# XibecaModuleBottom.net
KiCad netlist of a schematic drawn in EAGLE
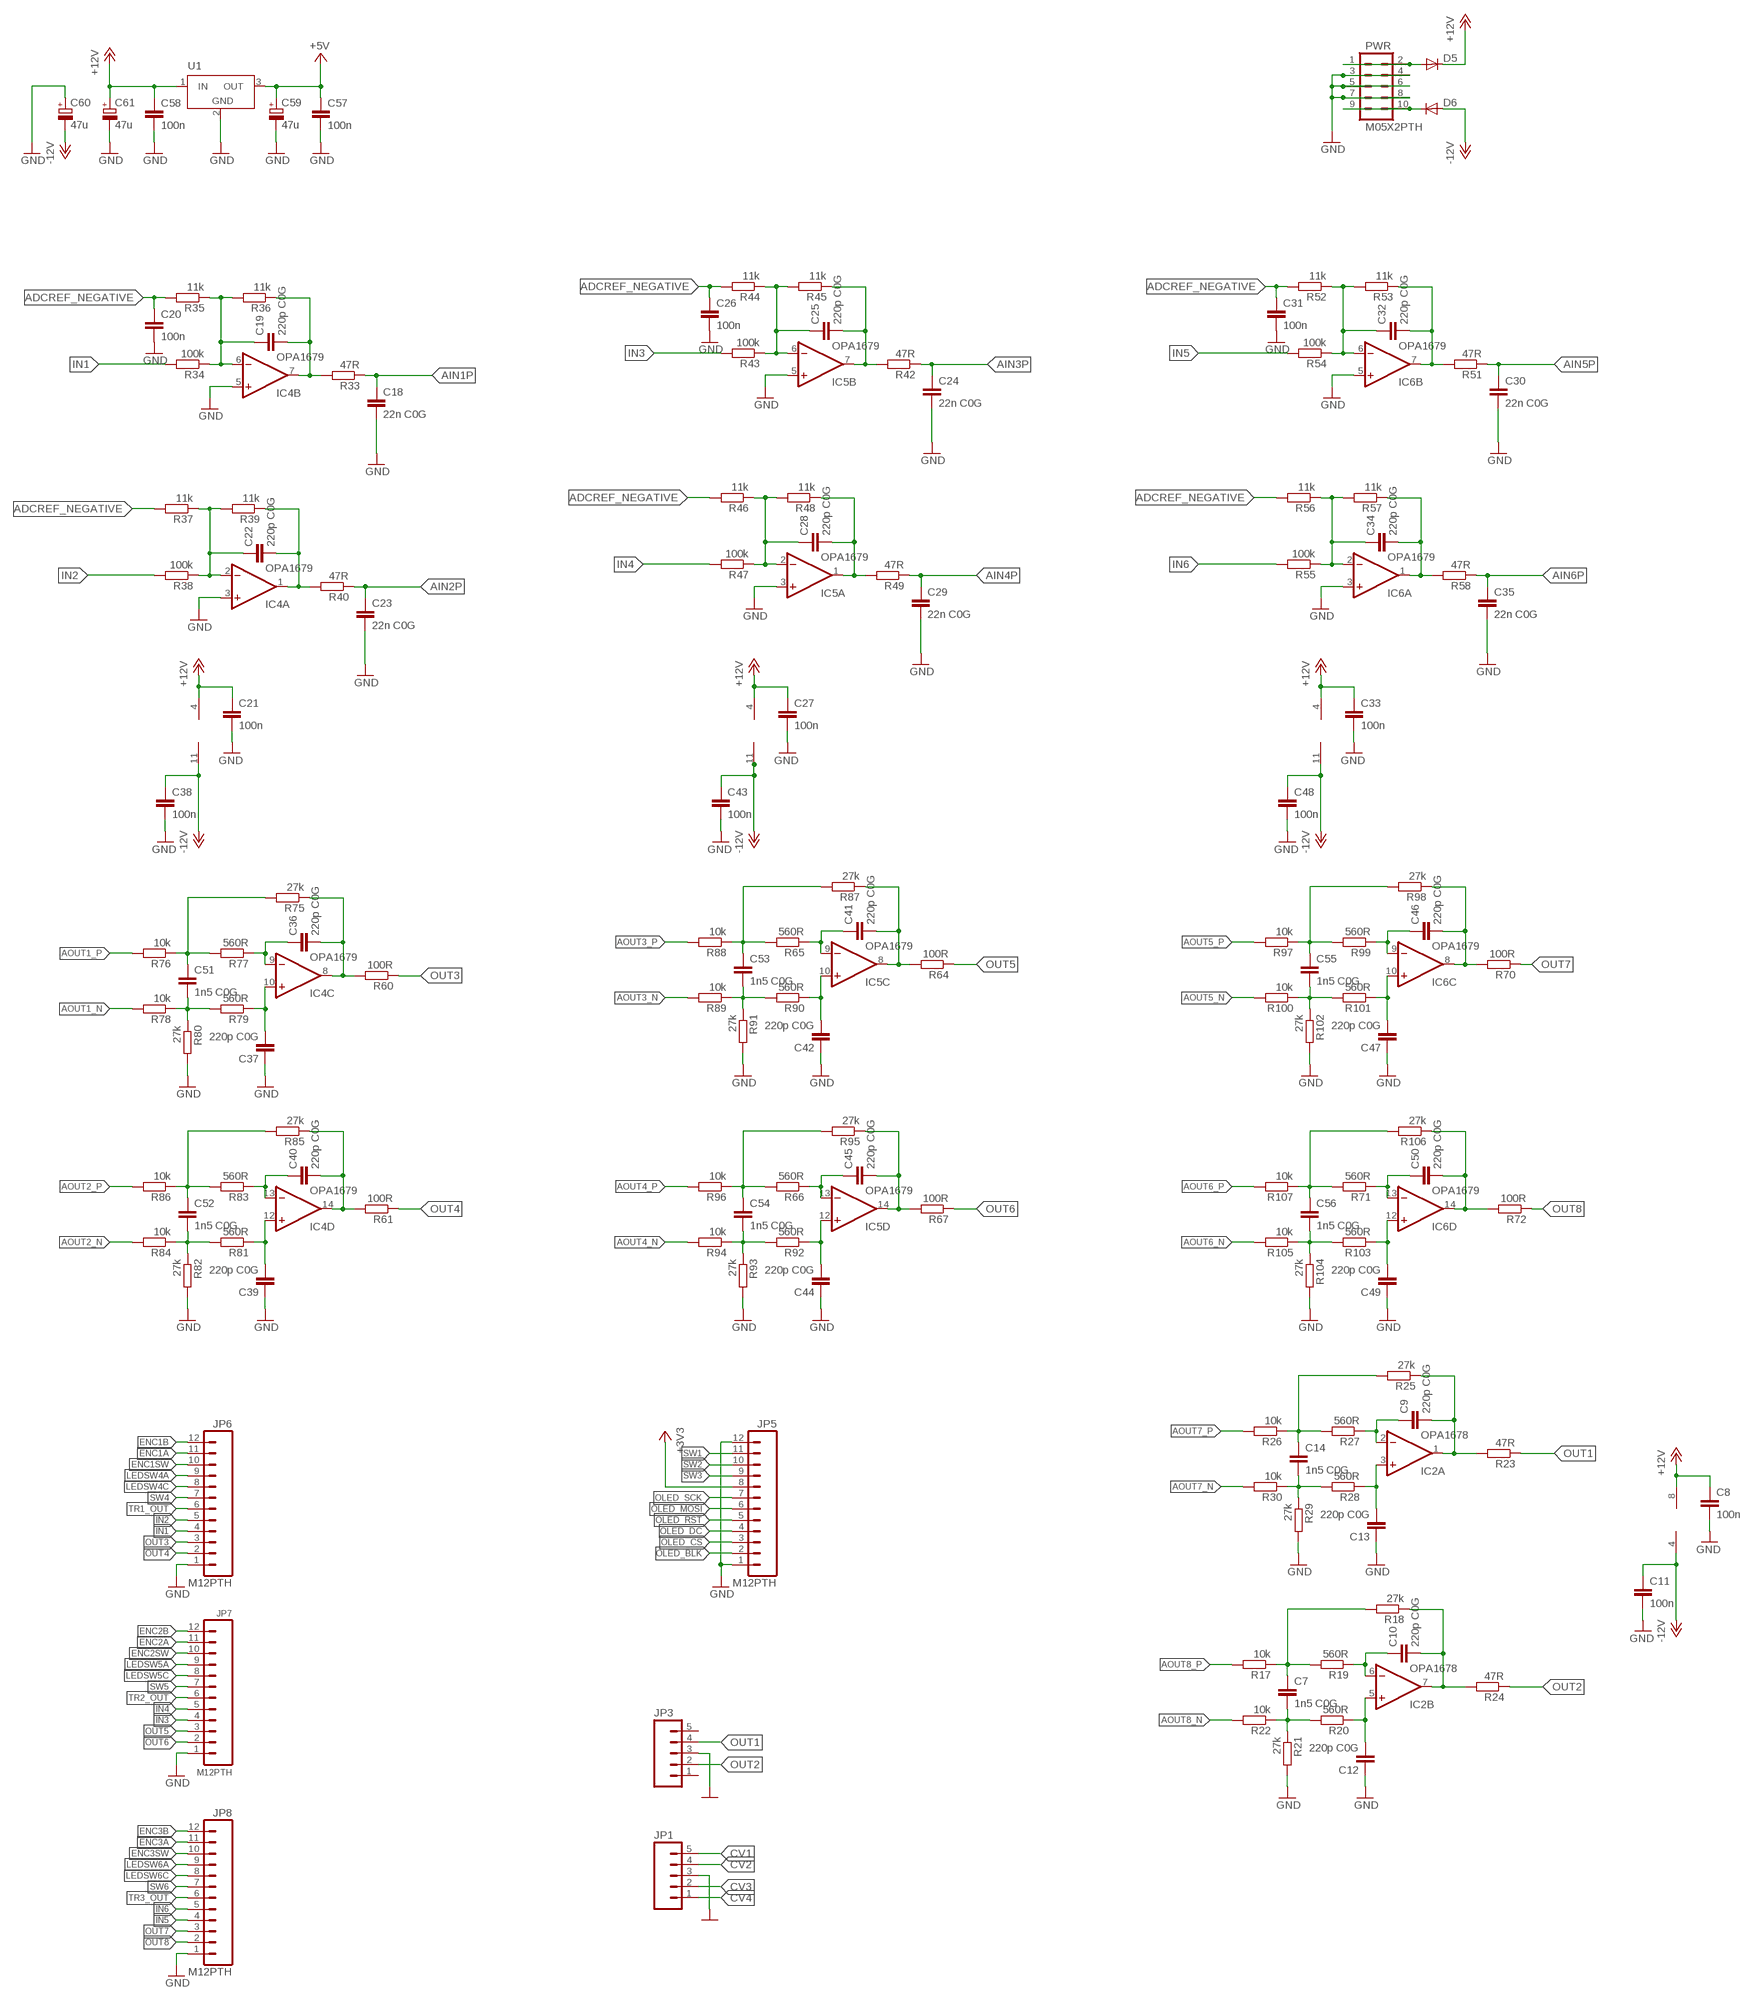
[diagram p0: schematic, sheet 1, part 1 of 2]
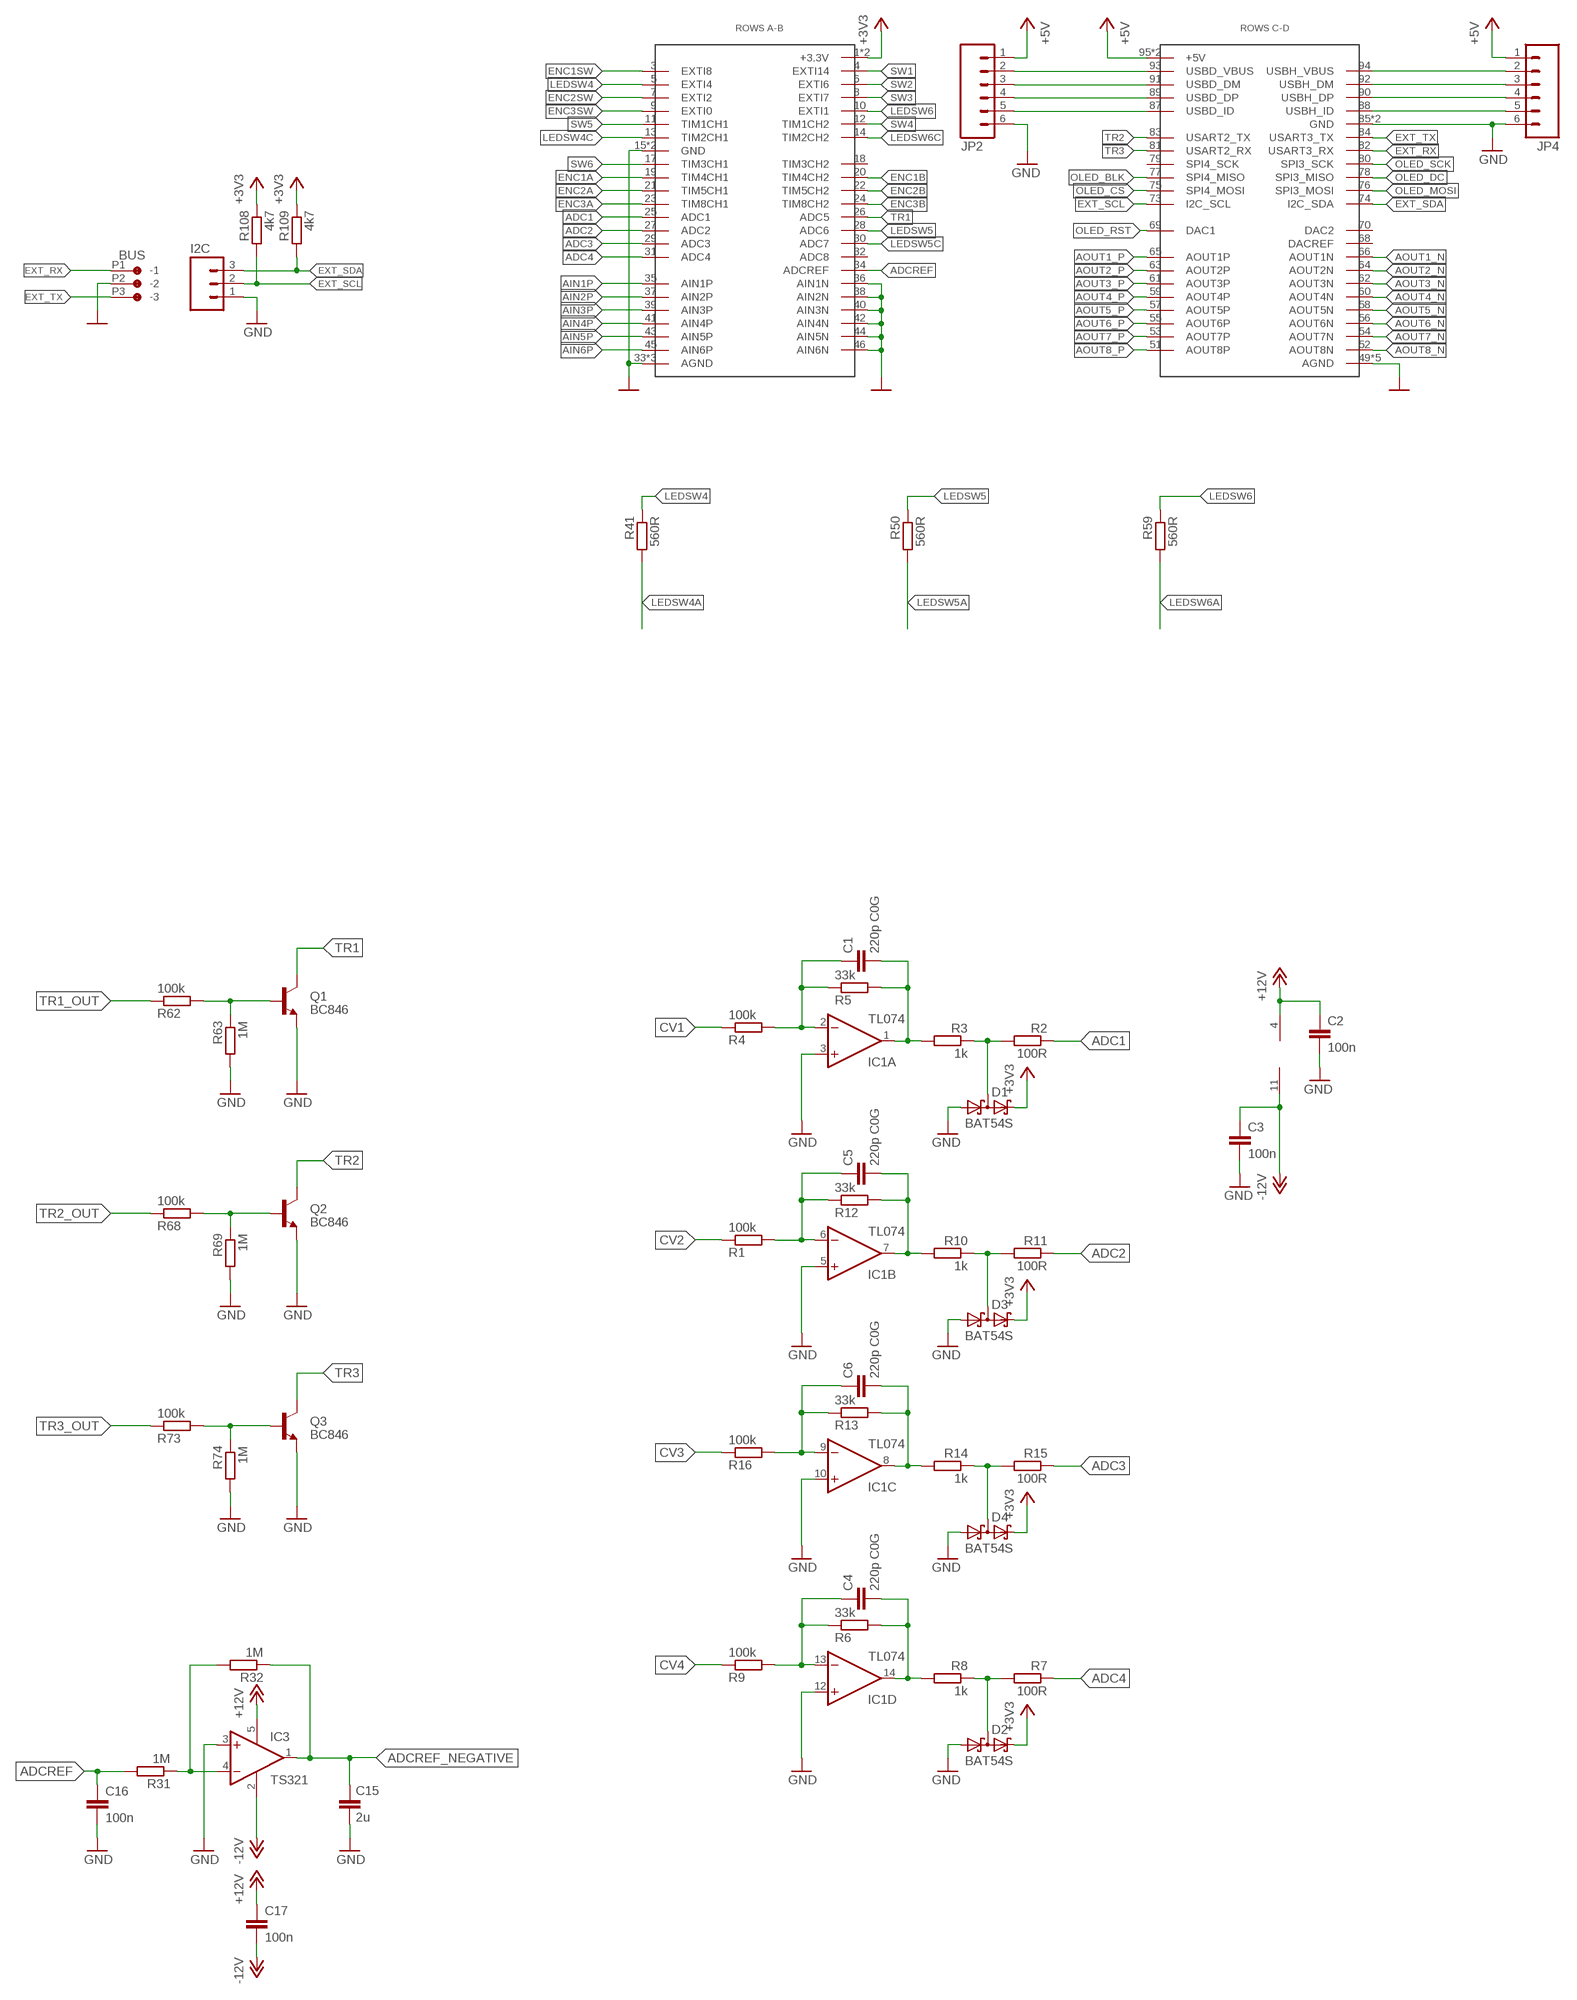
[diagram p1: schematic, sheet 1, part 2 of 2]

(export (version "E")
  (design (tool "Eeschema 10.0.6"))
  (components
    (comp (ref "BUS")
      (value "CON-JST_PH_3W")
      (footprint "eagle-import:CON-JST_PH_3W")
      (libsource (lib "eagle-import") (part "CON-JST_PH_3W"))
    )
    (comp (ref "C1")
      (value "220p C0G")
      (footprint "eagle-import:C0603")
      (libsource (lib "eagle-import") (part "Rebel_15457297_C-EUC0603"))
    )
    (comp (ref "C2")
      (value "100n")
      (footprint "eagle-import:C0603")
      (libsource (lib "eagle-import") (part "Rebel_15457297_C-EUC0603"))
    )
    (comp (ref "C3")
      (value "100n")
      (footprint "eagle-import:C0603")
      (libsource (lib "eagle-import") (part "Rebel_15457297_C-EUC0603"))
    )
    (comp (ref "C4")
      (value "220p C0G")
      (footprint "eagle-import:C0603")
      (libsource (lib "eagle-import") (part "Rebel_15457297_C-EUC0603"))
    )
    (comp (ref "C5")
      (value "220p C0G")
      (footprint "eagle-import:C0603")
      (libsource (lib "eagle-import") (part "Rebel_15457297_C-EUC0603"))
    )
    (comp (ref "C6")
      (value "220p C0G")
      (footprint "eagle-import:C0603")
      (libsource (lib "eagle-import") (part "Rebel_15457297_C-EUC0603"))
    )
    (comp (ref "C7")
      (value "1n5 C0G")
      (footprint "eagle-import:C0603")
      (libsource (lib "eagle-import") (part "Rebel_15457297_C-EUC0603"))
    )
    (comp (ref "C8")
      (value "100n")
      (footprint "eagle-import:C0603")
      (libsource (lib "eagle-import") (part "Rebel_15457297_C-EUC0603"))
    )
    (comp (ref "C9")
      (value "220p C0G")
      (footprint "eagle-import:C0603")
      (libsource (lib "eagle-import") (part "Rebel_15457297_C-EUC0603"))
    )
    (comp (ref "C10")
      (value "220p C0G")
      (footprint "eagle-import:C0603")
      (libsource (lib "eagle-import") (part "Rebel_15457297_C-EUC0603"))
    )
    (comp (ref "C11")
      (value "100n")
      (footprint "eagle-import:C0603")
      (libsource (lib "eagle-import") (part "Rebel_15457297_C-EUC0603"))
    )
    (comp (ref "C12")
      (value "220p C0G")
      (footprint "eagle-import:C0603")
      (libsource (lib "eagle-import") (part "Rebel_15457297_C-EUC0603"))
    )
    (comp (ref "C13")
      (value "220p C0G")
      (footprint "eagle-import:C0603")
      (libsource (lib "eagle-import") (part "Rebel_15457297_C-EUC0603"))
    )
    (comp (ref "C14")
      (value "1n5 C0G")
      (footprint "eagle-import:C0603")
      (libsource (lib "eagle-import") (part "Rebel_15457297_C-EUC0603"))
    )
    (comp (ref "C15")
      (value "2u")
      (footprint "eagle-import:C0603")
      (libsource (lib "eagle-import") (part "C-EUC0603"))
    )
    (comp (ref "C16")
      (value "100n")
      (footprint "eagle-import:C0603")
      (libsource (lib "eagle-import") (part "Rebel_15457297_C-EUC0603"))
    )
    (comp (ref "C17")
      (value "100n")
      (footprint "eagle-import:C0603")
      (libsource (lib "eagle-import") (part "Rebel_15457297_C-EUC0603"))
    )
    (comp (ref "C18")
      (value "22n C0G")
      (footprint "eagle-import:C0603")
      (libsource (lib "eagle-import") (part "Rebel_15457297_C-EUC0603"))
    )
    (comp (ref "C19")
      (value "220p C0G")
      (footprint "eagle-import:C0603")
      (libsource (lib "eagle-import") (part "Rebel_15457297_C-EUC0603"))
    )
    (comp (ref "C20")
      (value "100n")
      (footprint "eagle-import:C0603")
      (libsource (lib "eagle-import") (part "Rebel_15457297_C-EUC0603"))
    )
    (comp (ref "C21")
      (value "100n")
      (footprint "eagle-import:C0603")
      (libsource (lib "eagle-import") (part "C-EUC0603"))
    )
    (comp (ref "C22")
      (value "220p C0G")
      (footprint "eagle-import:C0603")
      (libsource (lib "eagle-import") (part "Rebel_15457297_C-EUC0603"))
    )
    (comp (ref "C23")
      (value "22n C0G")
      (footprint "eagle-import:C0603")
      (libsource (lib "eagle-import") (part "Rebel_15457297_C-EUC0603"))
    )
    (comp (ref "C24")
      (value "22n C0G")
      (footprint "eagle-import:C0603")
      (libsource (lib "eagle-import") (part "Rebel_15457297_C-EUC0603"))
    )
    (comp (ref "C25")
      (value "220p C0G")
      (footprint "eagle-import:C0603")
      (libsource (lib "eagle-import") (part "Rebel_15457297_C-EUC0603"))
    )
    (comp (ref "C26")
      (value "100n")
      (footprint "eagle-import:C0603")
      (libsource (lib "eagle-import") (part "Rebel_15457297_C-EUC0603"))
    )
    (comp (ref "C27")
      (value "100n")
      (footprint "eagle-import:C0603")
      (libsource (lib "eagle-import") (part "Rebel_15457297_C-EUC0603"))
    )
    (comp (ref "C28")
      (value "220p C0G")
      (footprint "eagle-import:C0603")
      (libsource (lib "eagle-import") (part "Rebel_15457297_C-EUC0603"))
    )
    (comp (ref "C29")
      (value "22n C0G")
      (footprint "eagle-import:C0603")
      (libsource (lib "eagle-import") (part "Rebel_15457297_C-EUC0603"))
    )
    (comp (ref "C30")
      (value "22n C0G")
      (footprint "eagle-import:C0603")
      (libsource (lib "eagle-import") (part "Rebel_15457297_C-EUC0603"))
    )
    (comp (ref "C31")
      (value "100n")
      (footprint "eagle-import:C0603")
      (libsource (lib "eagle-import") (part "Rebel_15457297_C-EUC0603"))
    )
    (comp (ref "C32")
      (value "220p C0G")
      (footprint "eagle-import:C0603")
      (libsource (lib "eagle-import") (part "Rebel_15457297_C-EUC0603"))
    )
    (comp (ref "C33")
      (value "100n")
      (footprint "eagle-import:C0603")
      (libsource (lib "eagle-import") (part "C-EUC0603"))
    )
    (comp (ref "C34")
      (value "220p C0G")
      (footprint "eagle-import:C0603")
      (libsource (lib "eagle-import") (part "Rebel_15457297_C-EUC0603"))
    )
    (comp (ref "C35")
      (value "22n C0G")
      (footprint "eagle-import:C0603")
      (libsource (lib "eagle-import") (part "Rebel_15457297_C-EUC0603"))
    )
    (comp (ref "C36")
      (value "220p C0G")
      (footprint "eagle-import:C0603")
      (libsource (lib "eagle-import") (part "Rebel_15457297_C-EUC0603"))
    )
    (comp (ref "C37")
      (value "220p C0G")
      (footprint "eagle-import:C0603")
      (libsource (lib "eagle-import") (part "Rebel_15457297_C-EUC0603"))
    )
    (comp (ref "C38")
      (value "100n")
      (footprint "eagle-import:C0603")
      (libsource (lib "eagle-import") (part "C-EUC0603"))
    )
    (comp (ref "C39")
      (value "220p C0G")
      (footprint "eagle-import:C0603")
      (libsource (lib "eagle-import") (part "Rebel_15457297_C-EUC0603"))
    )
    (comp (ref "C40")
      (value "220p C0G")
      (footprint "eagle-import:C0603")
      (libsource (lib "eagle-import") (part "Rebel_15457297_C-EUC0603"))
    )
    (comp (ref "C41")
      (value "220p C0G")
      (footprint "eagle-import:C0603")
      (libsource (lib "eagle-import") (part "Rebel_15457297_C-EUC0603"))
    )
    (comp (ref "C42")
      (value "220p C0G")
      (footprint "eagle-import:C0603")
      (libsource (lib "eagle-import") (part "Rebel_15457297_C-EUC0603"))
    )
    (comp (ref "C43")
      (value "100n")
      (footprint "eagle-import:C0603")
      (libsource (lib "eagle-import") (part "Rebel_15457297_C-EUC0603"))
    )
    (comp (ref "C44")
      (value "220p C0G")
      (footprint "eagle-import:C0603")
      (libsource (lib "eagle-import") (part "Rebel_15457297_C-EUC0603"))
    )
    (comp (ref "C45")
      (value "220p C0G")
      (footprint "eagle-import:C0603")
      (libsource (lib "eagle-import") (part "Rebel_15457297_C-EUC0603"))
    )
    (comp (ref "C46")
      (value "220p C0G")
      (footprint "eagle-import:C0603")
      (libsource (lib "eagle-import") (part "Rebel_15457297_C-EUC0603"))
    )
    (comp (ref "C47")
      (value "220p C0G")
      (footprint "eagle-import:C0603")
      (libsource (lib "eagle-import") (part "Rebel_15457297_C-EUC0603"))
    )
    (comp (ref "C48")
      (value "100n")
      (footprint "eagle-import:C0603")
      (libsource (lib "eagle-import") (part "C-EUC0603"))
    )
    (comp (ref "C49")
      (value "220p C0G")
      (footprint "eagle-import:C0603")
      (libsource (lib "eagle-import") (part "Rebel_15457297_C-EUC0603"))
    )
    (comp (ref "C50")
      (value "220p C0G")
      (footprint "eagle-import:C0603")
      (libsource (lib "eagle-import") (part "Rebel_15457297_C-EUC0603"))
    )
    (comp (ref "C51")
      (value "1n5 C0G")
      (footprint "eagle-import:C0603")
      (libsource (lib "eagle-import") (part "Rebel_15457297_C-EUC0603"))
    )
    (comp (ref "C52")
      (value "1n5 C0G")
      (footprint "eagle-import:C0603")
      (libsource (lib "eagle-import") (part "Rebel_15457297_C-EUC0603"))
    )
    (comp (ref "C53")
      (value "1n5 C0G")
      (footprint "eagle-import:C0603")
      (libsource (lib "eagle-import") (part "Rebel_15457297_C-EUC0603"))
    )
    (comp (ref "C54")
      (value "1n5 C0G")
      (footprint "eagle-import:C0603")
      (libsource (lib "eagle-import") (part "Rebel_15457297_C-EUC0603"))
    )
    (comp (ref "C55")
      (value "1n5 C0G")
      (footprint "eagle-import:C0603")
      (libsource (lib "eagle-import") (part "Rebel_15457297_C-EUC0603"))
    )
    (comp (ref "C56")
      (value "1n5 C0G")
      (footprint "eagle-import:C0603")
      (libsource (lib "eagle-import") (part "Rebel_15457297_C-EUC0603"))
    )
    (comp (ref "C57")
      (value "100n")
      (footprint "eagle-import:C0603")
      (libsource (lib "eagle-import") (part "Rebel_15457297_C-EUC0603"))
    )
    (comp (ref "C58")
      (value "100n")
      (footprint "eagle-import:C0603")
      (libsource (lib "eagle-import") (part "Rebel_15457297_C-EUC0603"))
    )
    (comp (ref "C59")
      (value "47u")
      (footprint "eagle-import:E5-8,5")
      (libsource (lib "eagle-import") (part "CPOL-EUE5-8.5"))
    )
    (comp (ref "C60")
      (value "47u")
      (footprint "eagle-import:E5-8,5")
      (libsource (lib "eagle-import") (part "CPOL-EUE5-8.5"))
    )
    (comp (ref "C61")
      (value "47u")
      (footprint "eagle-import:E5-8,5")
      (libsource (lib "eagle-import") (part "CPOL-EUE5-8.5"))
    )
    (comp (ref "D1")
      (value "BAT54S")
      (footprint "eagle-import:SOT23")
      (libsource (lib "eagle-import") (part "BAT54S"))
    )
    (comp (ref "D2")
      (value "BAT54S")
      (footprint "eagle-import:SOT23")
      (libsource (lib "eagle-import") (part "BAT54S"))
    )
    (comp (ref "D3")
      (value "BAT54S")
      (footprint "eagle-import:SOT23")
      (libsource (lib "eagle-import") (part "BAT54S"))
    )
    (comp (ref "D4")
      (value "BAT54S")
      (footprint "eagle-import:SOT23")
      (libsource (lib "eagle-import") (part "BAT54S"))
    )
    (comp (ref "D5")
      (value "DIODE1N4001")
      (footprint "eagle-import:DIODE-1N4001")
      (libsource (lib "eagle-import") (part "DIODE1N4001"))
    )
    (comp (ref "D6")
      (value "DIODE1N4001")
      (footprint "eagle-import:DIODE-1N4001")
      (libsource (lib "eagle-import") (part "DIODE1N4001"))
    )
    (comp (ref "I2C")
      (value "M03PTH")
      (footprint "eagle-import:1X03")
      (libsource (lib "eagle-import") (part "M03PTH"))
    )
    (comp (ref "IC1")
      (value "TL074")
      (footprint "eagle-import:SO14")
      (libsource (lib "eagle-import") (part "QUAD_OPAMPD"))
    )
    (comp (ref "IC2")
      (value "OPA1678")
      (footprint "eagle-import:SO08")
      (libsource (lib "eagle-import") (part "TL072D"))
    )
    (comp (ref "IC3")
      (value "TS321")
      (footprint "eagle-import:SOT23-5")
      (libsource (lib "eagle-import") (part "OPA725DBV"))
    )
    (comp (ref "IC4")
      (value "OPA1679")
      (footprint "eagle-import:SO14")
      (libsource (lib "eagle-import") (part "TL074D"))
    )
    (comp (ref "IC5")
      (value "OPA1679")
      (footprint "eagle-import:SO14")
      (libsource (lib "eagle-import") (part "TL074D"))
    )
    (comp (ref "IC6")
      (value "OPA1679")
      (footprint "eagle-import:SO14")
      (libsource (lib "eagle-import") (part "TL074D"))
    )
    (comp (ref "JP1")
      (value "M05PTH")
      (footprint "eagle-import:1X05")
      (libsource (lib "eagle-import") (part "M05PTH"))
    )
    (comp (ref "JP2")
      (value "M06SIP")
      (footprint "eagle-import:1X06")
      (libsource (lib "eagle-import") (part "M06SIP"))
    )
    (comp (ref "JP3")
      (value "M05PTH")
      (footprint "eagle-import:1X05")
      (libsource (lib "eagle-import") (part "M05PTH"))
    )
    (comp (ref "JP4")
      (value "M06SIP")
      (footprint "eagle-import:1X06")
      (libsource (lib "eagle-import") (part "M06SIP"))
    )
    (comp (ref "JP5")
      (value "M12PTH")
      (footprint "eagle-import:1X12")
      (libsource (lib "eagle-import") (part "M12PTH"))
    )
    (comp (ref "JP6")
      (value "M12PTH")
      (footprint "eagle-import:1X12")
      (libsource (lib "eagle-import") (part "M12PTH"))
    )
    (comp (ref "JP7")
      (value "M12PTH")
      (footprint "eagle-import:1X12")
      (libsource (lib "eagle-import") (part "M12PTH"))
    )
    (comp (ref "JP8")
      (value "M12PTH")
      (footprint "eagle-import:1X12")
      (libsource (lib "eagle-import") (part "M12PTH"))
    )
    (comp (ref "PWR")
      (value "M05X2PTH")
      (footprint "eagle-import:AVR_ICSP")
      (libsource (lib "eagle-import") (part "M05X2PTH"))
    )
    (comp (ref "Q1")
      (value "BC846")
      (footprint "eagle-import:SOT23")
      (libsource (lib "eagle-import") (part "BC846"))
    )
    (comp (ref "Q2")
      (value "BC846")
      (footprint "eagle-import:SOT23")
      (libsource (lib "eagle-import") (part "BC846"))
    )
    (comp (ref "Q3")
      (value "BC846")
      (footprint "eagle-import:SOT23")
      (libsource (lib "eagle-import") (part "BC846"))
    )
    (comp (ref "R1")
      (value "100k")
      (footprint "eagle-import:0603")
      (libsource (lib "eagle-import") (part "R-EU_R0603"))
    )
    (comp (ref "R2")
      (value "100R")
      (footprint "eagle-import:0603")
      (libsource (lib "eagle-import") (part "R-EU_R0603"))
    )
    (comp (ref "R3")
      (value "1k")
      (footprint "eagle-import:0603")
      (libsource (lib "eagle-import") (part "R-EU_R0603"))
    )
    (comp (ref "R4")
      (value "100k")
      (footprint "eagle-import:0603")
      (libsource (lib "eagle-import") (part "R-EU_R0603"))
    )
    (comp (ref "R5")
      (value "33k")
      (footprint "eagle-import:0603")
      (libsource (lib "eagle-import") (part "R-EU_R0603"))
    )
    (comp (ref "R6")
      (value "33k")
      (footprint "eagle-import:0603")
      (libsource (lib "eagle-import") (part "R-EU_R0603"))
    )
    (comp (ref "R7")
      (value "100R")
      (footprint "eagle-import:0603")
      (libsource (lib "eagle-import") (part "R-EU_R0603"))
    )
    (comp (ref "R8")
      (value "1k")
      (footprint "eagle-import:0603")
      (libsource (lib "eagle-import") (part "R-EU_R0603"))
    )
    (comp (ref "R9")
      (value "100k")
      (footprint "eagle-import:0603")
      (libsource (lib "eagle-import") (part "R-EU_R0603"))
    )
    (comp (ref "R10")
      (value "1k")
      (footprint "eagle-import:0603")
      (libsource (lib "eagle-import") (part "R-EU_R0603"))
    )
    (comp (ref "R11")
      (value "100R")
      (footprint "eagle-import:0603")
      (libsource (lib "eagle-import") (part "R-EU_R0603"))
    )
    (comp (ref "R12")
      (value "33k")
      (footprint "eagle-import:0603")
      (libsource (lib "eagle-import") (part "R-EU_R0603"))
    )
    (comp (ref "R13")
      (value "33k")
      (footprint "eagle-import:0603")
      (libsource (lib "eagle-import") (part "R-EU_R0603"))
    )
    (comp (ref "R14")
      (value "1k")
      (footprint "eagle-import:0603")
      (libsource (lib "eagle-import") (part "R-EU_R0603"))
    )
    (comp (ref "R15")
      (value "100R")
      (footprint "eagle-import:0603")
      (libsource (lib "eagle-import") (part "R-EU_R0603"))
    )
    (comp (ref "R16")
      (value "100k")
      (footprint "eagle-import:0603")
      (libsource (lib "eagle-import") (part "R-EU_R0603"))
    )
    (comp (ref "R17")
      (value "10k")
      (footprint "eagle-import:0603")
      (libsource (lib "eagle-import") (part "R-EU_R0603"))
    )
    (comp (ref "R18")
      (value "27k")
      (footprint "eagle-import:0603")
      (libsource (lib "eagle-import") (part "R-EU_R0603"))
    )
    (comp (ref "R19")
      (value "560R")
      (footprint "eagle-import:0603")
      (libsource (lib "eagle-import") (part "R-EU_R0603"))
    )
    (comp (ref "R20")
      (value "560R")
      (footprint "eagle-import:0603")
      (libsource (lib "eagle-import") (part "R-EU_R0603"))
    )
    (comp (ref "R21")
      (value "27k")
      (footprint "eagle-import:0603")
      (libsource (lib "eagle-import") (part "R-EU_R0603"))
    )
    (comp (ref "R22")
      (value "10k")
      (footprint "eagle-import:0603")
      (libsource (lib "eagle-import") (part "R-EU_R0603"))
    )
    (comp (ref "R23")
      (value "47R")
      (footprint "eagle-import:0603")
      (libsource (lib "eagle-import") (part "R-EU_R0603"))
    )
    (comp (ref "R24")
      (value "47R")
      (footprint "eagle-import:0603")
      (libsource (lib "eagle-import") (part "R-EU_R0603"))
    )
    (comp (ref "R25")
      (value "27k")
      (footprint "eagle-import:0603")
      (libsource (lib "eagle-import") (part "R-EU_R0603"))
    )
    (comp (ref "R26")
      (value "10k")
      (footprint "eagle-import:0603")
      (libsource (lib "eagle-import") (part "R-EU_R0603"))
    )
    (comp (ref "R27")
      (value "560R")
      (footprint "eagle-import:0603")
      (libsource (lib "eagle-import") (part "R-EU_R0603"))
    )
    (comp (ref "R28")
      (value "560R")
      (footprint "eagle-import:0603")
      (libsource (lib "eagle-import") (part "R-EU_R0603"))
    )
    (comp (ref "R29")
      (value "27k")
      (footprint "eagle-import:0603")
      (libsource (lib "eagle-import") (part "R-EU_R0603"))
    )
    (comp (ref "R30")
      (value "10k")
      (footprint "eagle-import:0603")
      (libsource (lib "eagle-import") (part "R-EU_R0603"))
    )
    (comp (ref "R31")
      (value "1M")
      (footprint "eagle-import:0603")
      (libsource (lib "eagle-import") (part "R-EU_R0603"))
    )
    (comp (ref "R32")
      (value "1M")
      (footprint "eagle-import:0603")
      (libsource (lib "eagle-import") (part "R-EU_R0603"))
    )
    (comp (ref "R33")
      (value "47R")
      (footprint "eagle-import:0603")
      (libsource (lib "eagle-import") (part "R-EU_R0603"))
    )
    (comp (ref "R34")
      (value "100k")
      (footprint "eagle-import:0603")
      (libsource (lib "eagle-import") (part "R-EU_R0603"))
    )
    (comp (ref "R35")
      (value "11k")
      (footprint "eagle-import:0603")
      (libsource (lib "eagle-import") (part "R-EU_R0603"))
    )
    (comp (ref "R36")
      (value "11k")
      (footprint "eagle-import:0603")
      (libsource (lib "eagle-import") (part "R-EU_R0603"))
    )
    (comp (ref "R37")
      (value "11k")
      (footprint "eagle-import:0603")
      (libsource (lib "eagle-import") (part "R-EU_R0603"))
    )
    (comp (ref "R38")
      (value "100k")
      (footprint "eagle-import:0603")
      (libsource (lib "eagle-import") (part "R-EU_R0603"))
    )
    (comp (ref "R39")
      (value "11k")
      (footprint "eagle-import:0603")
      (libsource (lib "eagle-import") (part "R-EU_R0603"))
    )
    (comp (ref "R40")
      (value "47R")
      (footprint "eagle-import:0603")
      (libsource (lib "eagle-import") (part "R-EU_R0603"))
    )
    (comp (ref "R41")
      (value "560R")
      (footprint "eagle-import:0603")
      (libsource (lib "eagle-import") (part "R-EU_R0603"))
    )
    (comp (ref "R42")
      (value "47R")
      (footprint "eagle-import:0603")
      (libsource (lib "eagle-import") (part "R-EU_R0603"))
    )
    (comp (ref "R43")
      (value "100k")
      (footprint "eagle-import:0603")
      (libsource (lib "eagle-import") (part "R-EU_R0603"))
    )
    (comp (ref "R44")
      (value "11k")
      (footprint "eagle-import:0603")
      (libsource (lib "eagle-import") (part "R-EU_R0603"))
    )
    (comp (ref "R45")
      (value "11k")
      (footprint "eagle-import:0603")
      (libsource (lib "eagle-import") (part "R-EU_R0603"))
    )
    (comp (ref "R46")
      (value "11k")
      (footprint "eagle-import:0603")
      (libsource (lib "eagle-import") (part "R-EU_R0603"))
    )
    (comp (ref "R47")
      (value "100k")
      (footprint "eagle-import:0603")
      (libsource (lib "eagle-import") (part "R-EU_R0603"))
    )
    (comp (ref "R48")
      (value "11k")
      (footprint "eagle-import:0603")
      (libsource (lib "eagle-import") (part "R-EU_R0603"))
    )
    (comp (ref "R49")
      (value "47R")
      (footprint "eagle-import:0603")
      (libsource (lib "eagle-import") (part "R-EU_R0603"))
    )
    (comp (ref "R50")
      (value "560R")
      (footprint "eagle-import:0603")
      (libsource (lib "eagle-import") (part "R-EU_R0603"))
    )
    (comp (ref "R51")
      (value "47R")
      (footprint "eagle-import:0603")
      (libsource (lib "eagle-import") (part "R-EU_R0603"))
    )
    (comp (ref "R52")
      (value "11k")
      (footprint "eagle-import:0603")
      (libsource (lib "eagle-import") (part "R-EU_R0603"))
    )
    (comp (ref "R53")
      (value "11k")
      (footprint "eagle-import:0603")
      (libsource (lib "eagle-import") (part "R-EU_R0603"))
    )
    (comp (ref "R54")
      (value "100k")
      (footprint "eagle-import:0603")
      (libsource (lib "eagle-import") (part "R-EU_R0603"))
    )
    (comp (ref "R55")
      (value "100k")
      (footprint "eagle-import:0603")
      (libsource (lib "eagle-import") (part "R-EU_R0603"))
    )
    (comp (ref "R56")
      (value "11k")
      (footprint "eagle-import:0603")
      (libsource (lib "eagle-import") (part "R-EU_R0603"))
    )
    (comp (ref "R57")
      (value "11k")
      (footprint "eagle-import:0603")
      (libsource (lib "eagle-import") (part "R-EU_R0603"))
    )
    (comp (ref "R58")
      (value "47R")
      (footprint "eagle-import:0603")
      (libsource (lib "eagle-import") (part "R-EU_R0603"))
    )
    (comp (ref "R59")
      (value "560R")
      (footprint "eagle-import:0603")
      (libsource (lib "eagle-import") (part "R-EU_R0603"))
    )
    (comp (ref "R60")
      (value "100R")
      (footprint "eagle-import:0603")
      (libsource (lib "eagle-import") (part "R-EU_R0603"))
    )
    (comp (ref "R61")
      (value "100R")
      (footprint "eagle-import:0603")
      (libsource (lib "eagle-import") (part "R-EU_R0603"))
    )
    (comp (ref "R62")
      (value "100k")
      (footprint "eagle-import:0603")
      (libsource (lib "eagle-import") (part "R-EU_R0603"))
    )
    (comp (ref "R63")
      (value "1M")
      (footprint "eagle-import:0603")
      (libsource (lib "eagle-import") (part "R-EU_R0603"))
    )
    (comp (ref "R64")
      (value "100R")
      (footprint "eagle-import:0603")
      (libsource (lib "eagle-import") (part "R-EU_R0603"))
    )
    (comp (ref "R65")
      (value "560R")
      (footprint "eagle-import:0603")
      (libsource (lib "eagle-import") (part "R-EU_R0603"))
    )
    (comp (ref "R66")
      (value "560R")
      (footprint "eagle-import:0603")
      (libsource (lib "eagle-import") (part "R-EU_R0603"))
    )
    (comp (ref "R67")
      (value "100R")
      (footprint "eagle-import:0603")
      (libsource (lib "eagle-import") (part "R-EU_R0603"))
    )
    (comp (ref "R68")
      (value "100k")
      (footprint "eagle-import:0603")
      (libsource (lib "eagle-import") (part "R-EU_R0603"))
    )
    (comp (ref "R69")
      (value "1M")
      (footprint "eagle-import:0603")
      (libsource (lib "eagle-import") (part "R-EU_R0603"))
    )
    (comp (ref "R70")
      (value "100R")
      (footprint "eagle-import:0603")
      (libsource (lib "eagle-import") (part "R-EU_R0603"))
    )
    (comp (ref "R71")
      (value "560R")
      (footprint "eagle-import:0603")
      (libsource (lib "eagle-import") (part "R-EU_R0603"))
    )
    (comp (ref "R72")
      (value "100R")
      (footprint "eagle-import:0603")
      (libsource (lib "eagle-import") (part "R-EU_R0603"))
    )
    (comp (ref "R73")
      (value "100k")
      (footprint "eagle-import:0603")
      (libsource (lib "eagle-import") (part "R-EU_R0603"))
    )
    (comp (ref "R74")
      (value "1M")
      (footprint "eagle-import:0603")
      (libsource (lib "eagle-import") (part "R-EU_R0603"))
    )
    (comp (ref "R75")
      (value "27k")
      (footprint "eagle-import:0603")
      (libsource (lib "eagle-import") (part "R-EU_R0603"))
    )
    (comp (ref "R76")
      (value "10k")
      (footprint "eagle-import:0603")
      (libsource (lib "eagle-import") (part "R-EU_R0603"))
    )
    (comp (ref "R77")
      (value "560R")
      (footprint "eagle-import:0603")
      (libsource (lib "eagle-import") (part "R-EU_R0603"))
    )
    (comp (ref "R78")
      (value "10k")
      (footprint "eagle-import:0603")
      (libsource (lib "eagle-import") (part "R-EU_R0603"))
    )
    (comp (ref "R79")
      (value "560R")
      (footprint "eagle-import:0603")
      (libsource (lib "eagle-import") (part "R-EU_R0603"))
    )
    (comp (ref "R80")
      (value "27k")
      (footprint "eagle-import:0603")
      (libsource (lib "eagle-import") (part "R-EU_R0603"))
    )
    (comp (ref "R81")
      (value "560R")
      (footprint "eagle-import:0603")
      (libsource (lib "eagle-import") (part "R-EU_R0603"))
    )
    (comp (ref "R82")
      (value "27k")
      (footprint "eagle-import:0603")
      (libsource (lib "eagle-import") (part "R-EU_R0603"))
    )
    (comp (ref "R83")
      (value "560R")
      (footprint "eagle-import:0603")
      (libsource (lib "eagle-import") (part "R-EU_R0603"))
    )
    (comp (ref "R84")
      (value "10k")
      (footprint "eagle-import:0603")
      (libsource (lib "eagle-import") (part "R-EU_R0603"))
    )
    (comp (ref "R85")
      (value "27k")
      (footprint "eagle-import:0603")
      (libsource (lib "eagle-import") (part "R-EU_R0603"))
    )
    (comp (ref "R86")
      (value "10k")
      (footprint "eagle-import:0603")
      (libsource (lib "eagle-import") (part "R-EU_R0603"))
    )
    (comp (ref "R87")
      (value "27k")
      (footprint "eagle-import:0603")
      (libsource (lib "eagle-import") (part "R-EU_R0603"))
    )
    (comp (ref "R88")
      (value "10k")
      (footprint "eagle-import:0603")
      (libsource (lib "eagle-import") (part "R-EU_R0603"))
    )
    (comp (ref "R89")
      (value "10k")
      (footprint "eagle-import:0603")
      (libsource (lib "eagle-import") (part "R-EU_R0603"))
    )
    (comp (ref "R90")
      (value "560R")
      (footprint "eagle-import:0603")
      (libsource (lib "eagle-import") (part "R-EU_R0603"))
    )
    (comp (ref "R91")
      (value "27k")
      (footprint "eagle-import:0603")
      (libsource (lib "eagle-import") (part "R-EU_R0603"))
    )
    (comp (ref "R92")
      (value "560R")
      (footprint "eagle-import:0603")
      (libsource (lib "eagle-import") (part "R-EU_R0603"))
    )
    (comp (ref "R93")
      (value "27k")
      (footprint "eagle-import:0603")
      (libsource (lib "eagle-import") (part "R-EU_R0603"))
    )
    (comp (ref "R94")
      (value "10k")
      (footprint "eagle-import:0603")
      (libsource (lib "eagle-import") (part "R-EU_R0603"))
    )
    (comp (ref "R95")
      (value "27k")
      (footprint "eagle-import:0603")
      (libsource (lib "eagle-import") (part "R-EU_R0603"))
    )
    (comp (ref "R96")
      (value "10k")
      (footprint "eagle-import:0603")
      (libsource (lib "eagle-import") (part "R-EU_R0603"))
    )
    (comp (ref "R97")
      (value "10k")
      (footprint "eagle-import:0603")
      (libsource (lib "eagle-import") (part "R-EU_R0603"))
    )
    (comp (ref "R98")
      (value "27k")
      (footprint "eagle-import:0603")
      (libsource (lib "eagle-import") (part "R-EU_R0603"))
    )
    (comp (ref "R99")
      (value "560R")
      (footprint "eagle-import:0603")
      (libsource (lib "eagle-import") (part "R-EU_R0603"))
    )
    (comp (ref "R100")
      (value "10k")
      (footprint "eagle-import:0603")
      (libsource (lib "eagle-import") (part "R-EU_R0603"))
    )
    (comp (ref "R101")
      (value "560R")
      (footprint "eagle-import:0603")
      (libsource (lib "eagle-import") (part "R-EU_R0603"))
    )
    (comp (ref "R102")
      (value "27k")
      (footprint "eagle-import:0603")
      (libsource (lib "eagle-import") (part "R-EU_R0603"))
    )
    (comp (ref "R103")
      (value "560R")
      (footprint "eagle-import:0603")
      (libsource (lib "eagle-import") (part "R-EU_R0603"))
    )
    (comp (ref "R104")
      (value "27k")
      (footprint "eagle-import:0603")
      (libsource (lib "eagle-import") (part "R-EU_R0603"))
    )
    (comp (ref "R105")
      (value "10k")
      (footprint "eagle-import:0603")
      (libsource (lib "eagle-import") (part "R-EU_R0603"))
    )
    (comp (ref "R106")
      (value "27k")
      (footprint "eagle-import:0603")
      (libsource (lib "eagle-import") (part "R-EU_R0603"))
    )
    (comp (ref "R107")
      (value "10k")
      (footprint "eagle-import:0603")
      (libsource (lib "eagle-import") (part "R-EU_R0603"))
    )
    (comp (ref "R108")
      (value "4k7")
      (footprint "eagle-import:0603")
      (libsource (lib "eagle-import") (part "R-EU_R0603"))
    )
    (comp (ref "R109")
      (value "4k7")
      (footprint "eagle-import:0603")
      (libsource (lib "eagle-import") (part "R-EU_R0603"))
    )
    (comp (ref "U$2")
      (value "NOCTUA2NOCTUA2")
      (footprint "eagle-import:NOCTUA")
      (libsource (lib "eagle-import") (part "NOCTUA2NOCTUA2"))
    )
    (comp (ref "U1")
      (value "TSR-1-2450")
      (footprint "eagle-import:TSR-1-2450")
      (libsource (lib "eagle-import") (part "TSR-1-2450"))
    )
  )
  (nets
    (net (code "1") (name "+3V3") (class "Default")
      (node (ref "D1") (pin "2") (pinfunction "C2_2") (pintype "passive"))
      (node (ref "D2") (pin "2") (pinfunction "C2_2") (pintype "passive"))
      (node (ref "D3") (pin "2") (pinfunction "C2_2") (pintype "passive"))
      (node (ref "D4") (pin "2") (pinfunction "C2_2") (pintype "passive"))
      (node (ref "JP5") (pin "8") (pinfunction "8_8") (pintype "passive"))
      (node (ref "R108") (pin "1") (pinfunction "1_1") (pintype "passive"))
      (node (ref "R109") (pin "1") (pinfunction "1_1") (pintype "passive"))
      (node (ref "U$2") (pin "1") (pinfunction "+3.3V_1") (pintype "bidirectional"))
      (node (ref "U$2") (pin "2") (pinfunction "+3.3V_2") (pintype "bidirectional"))
    )
    (net (code "2") (name "+5V") (class "Default")
      (node (ref "C57") (pin "1") (pinfunction "1_1") (pintype "passive"))
      (node (ref "C59") (pin "+") (pinfunction "+_+") (pintype "passive"))
      (node (ref "JP2") (pin "1") (pinfunction "1_1") (pintype "passive"))
      (node (ref "JP4") (pin "1") (pinfunction "1_1") (pintype "passive"))
      (node (ref "U$2") (pin "95") (pinfunction "+5V_95") (pintype "bidirectional"))
      (node (ref "U$2") (pin "96") (pinfunction "+5V_96") (pintype "bidirectional"))
      (node (ref "U1") (pin "3") (pinfunction "OUT_3") (pintype "output"))
    )
    (net (code "3") (name "+12V") (class "Default")
      (node (ref "C17") (pin "1") (pinfunction "1_1") (pintype "passive"))
      (node (ref "C2") (pin "1") (pinfunction "1_1") (pintype "passive"))
      (node (ref "C21") (pin "1") (pinfunction "1_1") (pintype "passive"))
      (node (ref "C27") (pin "1") (pinfunction "1_1") (pintype "passive"))
      (node (ref "C33") (pin "1") (pinfunction "1_1") (pintype "passive"))
      (node (ref "C58") (pin "1") (pinfunction "1_1") (pintype "passive"))
      (node (ref "C61") (pin "+") (pinfunction "+_+") (pintype "passive"))
      (node (ref "C8") (pin "1") (pinfunction "1_1") (pintype "passive"))
      (node (ref "D5") (pin "C") (pinfunction "C_C") (pintype "passive"))
      (node (ref "IC1") (pin "4") (pinfunction "V+_4") (pintype "power_in"))
      (node (ref "IC2") (pin "8") (pinfunction "V+_8") (pintype "power_in"))
      (node (ref "IC3") (pin "5") (pinfunction "V+_5") (pintype "power_in"))
      (node (ref "IC4") (pin "4") (pinfunction "V+_4") (pintype "power_in"))
      (node (ref "IC5") (pin "4") (pinfunction "V+_4") (pintype "power_in"))
      (node (ref "IC6") (pin "4") (pinfunction "V+_4") (pintype "power_in"))
      (node (ref "U1") (pin "1") (pinfunction "IN_1") (pintype "input"))
    )
    (net (code "4") (name "-12V") (class "Default")
      (node (ref "C11") (pin "1") (pinfunction "1_1") (pintype "passive"))
      (node (ref "C17") (pin "2") (pinfunction "2_2") (pintype "passive"))
      (node (ref "C3") (pin "1") (pinfunction "1_1") (pintype "passive"))
      (node (ref "C38") (pin "1") (pinfunction "1_1") (pintype "passive"))
      (node (ref "C43") (pin "1") (pinfunction "1_1") (pintype "passive"))
      (node (ref "C48") (pin "1") (pinfunction "1_1") (pintype "passive"))
      (node (ref "C60") (pin "-") (pinfunction "-_-") (pintype "passive"))
      (node (ref "D6") (pin "A") (pinfunction "A_A") (pintype "passive"))
      (node (ref "IC1") (pin "11") (pinfunction "V-_11") (pintype "power_in"))
      (node (ref "IC2") (pin "4") (pinfunction "V-_4") (pintype "power_in"))
      (node (ref "IC3") (pin "2") (pinfunction "V-_2") (pintype "power_in"))
      (node (ref "IC4") (pin "11") (pinfunction "V-_11") (pintype "power_in"))
      (node (ref "IC5") (pin "11") (pinfunction "V-_11") (pintype "power_in"))
      (node (ref "IC6") (pin "11") (pinfunction "V-_11") (pintype "power_in"))
    )
    (net (code "5") (name "ADC1") (class "Default")
      (node (ref "R2") (pin "1") (pinfunction "1_1") (pintype "passive"))
      (node (ref "U$2") (pin "25") (pinfunction "ADC1_25") (pintype "bidirectional"))
    )
    (net (code "6") (name "ADC2") (class "Default")
      (node (ref "R11") (pin "1") (pinfunction "1_1") (pintype "passive"))
      (node (ref "U$2") (pin "27") (pinfunction "ADC2_27") (pintype "bidirectional"))
    )
    (net (code "7") (name "ADC3") (class "Default")
      (node (ref "R15") (pin "1") (pinfunction "1_1") (pintype "passive"))
      (node (ref "U$2") (pin "29") (pinfunction "ADC3_29") (pintype "bidirectional"))
    )
    (net (code "8") (name "ADC4") (class "Default")
      (node (ref "R7") (pin "1") (pinfunction "1_1") (pintype "passive"))
      (node (ref "U$2") (pin "31") (pinfunction "ADC4_31") (pintype "bidirectional"))
    )
    (net (code "9") (name "ADCREF") (class "Default")
      (node (ref "C16") (pin "1") (pinfunction "1_1") (pintype "passive"))
      (node (ref "R31") (pin "2") (pinfunction "2_2") (pintype "passive"))
      (node (ref "U$2") (pin "34") (pinfunction "ADCREF_34") (pintype "bidirectional"))
    )
    (net (code "10") (name "ADCREF_NEGATIVE") (class "Default")
      (node (ref "C15") (pin "1") (pinfunction "1_1") (pintype "passive"))
      (node (ref "C20") (pin "1") (pinfunction "1_1") (pintype "passive"))
      (node (ref "C26") (pin "1") (pinfunction "1_1") (pintype "passive"))
      (node (ref "C31") (pin "1") (pinfunction "1_1") (pintype "passive"))
      (node (ref "IC3") (pin "1") (pinfunction "OUT_1") (pintype "output"))
      (node (ref "R32") (pin "1") (pinfunction "1_1") (pintype "passive"))
      (node (ref "R35") (pin "2") (pinfunction "2_2") (pintype "passive"))
      (node (ref "R37") (pin "2") (pinfunction "2_2") (pintype "passive"))
      (node (ref "R44") (pin "2") (pinfunction "2_2") (pintype "passive"))
      (node (ref "R46") (pin "2") (pinfunction "2_2") (pintype "passive"))
      (node (ref "R52") (pin "2") (pinfunction "2_2") (pintype "passive"))
      (node (ref "R56") (pin "2") (pinfunction "2_2") (pintype "passive"))
    )
    (net (code "11") (name "AIN1P") (class "Default")
      (node (ref "C18") (pin "1") (pinfunction "1_1") (pintype "passive"))
      (node (ref "R33") (pin "1") (pinfunction "1_1") (pintype "passive"))
      (node (ref "U$2") (pin "35") (pinfunction "AIN1P_35") (pintype "bidirectional"))
    )
    (net (code "12") (name "AIN2P") (class "Default")
      (node (ref "C23") (pin "1") (pinfunction "1_1") (pintype "passive"))
      (node (ref "R40") (pin "1") (pinfunction "1_1") (pintype "passive"))
      (node (ref "U$2") (pin "37") (pinfunction "AIN2P_37") (pintype "bidirectional"))
    )
    (net (code "13") (name "AIN3P") (class "Default")
      (node (ref "C24") (pin "1") (pinfunction "1_1") (pintype "passive"))
      (node (ref "R42") (pin "1") (pinfunction "1_1") (pintype "passive"))
      (node (ref "U$2") (pin "39") (pinfunction "AIN3P_39") (pintype "bidirectional"))
    )
    (net (code "14") (name "AIN4P") (class "Default")
      (node (ref "C29") (pin "1") (pinfunction "1_1") (pintype "passive"))
      (node (ref "R49") (pin "1") (pinfunction "1_1") (pintype "passive"))
      (node (ref "U$2") (pin "41") (pinfunction "AIN4P_41") (pintype "bidirectional"))
    )
    (net (code "15") (name "AIN5P") (class "Default")
      (node (ref "C30") (pin "1") (pinfunction "1_1") (pintype "passive"))
      (node (ref "R51") (pin "1") (pinfunction "1_1") (pintype "passive"))
      (node (ref "U$2") (pin "43") (pinfunction "AIN5P_43") (pintype "bidirectional"))
    )
    (net (code "16") (name "AIN6P") (class "Default")
      (node (ref "C35") (pin "1") (pinfunction "1_1") (pintype "passive"))
      (node (ref "R58") (pin "1") (pinfunction "1_1") (pintype "passive"))
      (node (ref "U$2") (pin "45") (pinfunction "AIN6P_45") (pintype "bidirectional"))
    )
    (net (code "17") (name "AOUT1_N") (class "Default")
      (node (ref "R78") (pin "2") (pinfunction "2_2") (pintype "passive"))
      (node (ref "U$2") (pin "66") (pinfunction "AOUT1N_66") (pintype "bidirectional"))
    )
    (net (code "18") (name "AOUT1_P") (class "Default")
      (node (ref "R76") (pin "2") (pinfunction "2_2") (pintype "passive"))
      (node (ref "U$2") (pin "65") (pinfunction "AOUT1P_65") (pintype "bidirectional"))
    )
    (net (code "19") (name "AOUT2_N") (class "Default")
      (node (ref "R84") (pin "2") (pinfunction "2_2") (pintype "passive"))
      (node (ref "U$2") (pin "64") (pinfunction "AOUT2N_64") (pintype "bidirectional"))
    )
    (net (code "20") (name "AOUT2_P") (class "Default")
      (node (ref "R86") (pin "2") (pinfunction "2_2") (pintype "passive"))
      (node (ref "U$2") (pin "63") (pinfunction "AOUT2P_63") (pintype "bidirectional"))
    )
    (net (code "21") (name "AOUT3_N") (class "Default")
      (node (ref "R89") (pin "2") (pinfunction "2_2") (pintype "passive"))
      (node (ref "U$2") (pin "62") (pinfunction "AOUT3N_62") (pintype "bidirectional"))
    )
    (net (code "22") (name "AOUT3_P") (class "Default")
      (node (ref "R88") (pin "2") (pinfunction "2_2") (pintype "passive"))
      (node (ref "U$2") (pin "61") (pinfunction "AOUT3P_61") (pintype "bidirectional"))
    )
    (net (code "23") (name "AOUT4_N") (class "Default")
      (node (ref "R94") (pin "2") (pinfunction "2_2") (pintype "passive"))
      (node (ref "U$2") (pin "60") (pinfunction "AOUT4N_60") (pintype "bidirectional"))
    )
    (net (code "24") (name "AOUT4_P") (class "Default")
      (node (ref "R96") (pin "2") (pinfunction "2_2") (pintype "passive"))
      (node (ref "U$2") (pin "59") (pinfunction "AOUT4P_59") (pintype "bidirectional"))
    )
    (net (code "25") (name "AOUT5_N") (class "Default")
      (node (ref "R100") (pin "2") (pinfunction "2_2") (pintype "passive"))
      (node (ref "U$2") (pin "58") (pinfunction "AOUT5N_58") (pintype "bidirectional"))
    )
    (net (code "26") (name "AOUT5_P") (class "Default")
      (node (ref "R97") (pin "2") (pinfunction "2_2") (pintype "passive"))
      (node (ref "U$2") (pin "57") (pinfunction "AOUT5P_57") (pintype "bidirectional"))
    )
    (net (code "27") (name "AOUT6_N") (class "Default")
      (node (ref "R105") (pin "2") (pinfunction "2_2") (pintype "passive"))
      (node (ref "U$2") (pin "56") (pinfunction "AOUT6N_56") (pintype "bidirectional"))
    )
    (net (code "28") (name "AOUT6_P") (class "Default")
      (node (ref "R107") (pin "2") (pinfunction "2_2") (pintype "passive"))
      (node (ref "U$2") (pin "55") (pinfunction "AOUT6P_55") (pintype "bidirectional"))
    )
    (net (code "29") (name "AOUT7_N") (class "Default")
      (node (ref "R30") (pin "2") (pinfunction "2_2") (pintype "passive"))
      (node (ref "U$2") (pin "54") (pinfunction "AOUT7N_54") (pintype "bidirectional"))
    )
    (net (code "30") (name "AOUT7_P") (class "Default")
      (node (ref "R26") (pin "2") (pinfunction "2_2") (pintype "passive"))
      (node (ref "U$2") (pin "53") (pinfunction "AOUT7P_53") (pintype "bidirectional"))
    )
    (net (code "31") (name "AOUT8_N") (class "Default")
      (node (ref "R22") (pin "2") (pinfunction "2_2") (pintype "passive"))
      (node (ref "U$2") (pin "52") (pinfunction "AOUT8N_52") (pintype "bidirectional"))
    )
    (net (code "32") (name "AOUT8_P") (class "Default")
      (node (ref "R17") (pin "2") (pinfunction "2_2") (pintype "passive"))
      (node (ref "U$2") (pin "51") (pinfunction "AOUT8P_51") (pintype "bidirectional"))
    )
    (net (code "33") (name "CV1") (class "Default")
      (node (ref "JP1") (pin "5") (pinfunction "5_5") (pintype "passive"))
      (node (ref "R4") (pin "1") (pinfunction "1_1") (pintype "passive"))
    )
    (net (code "34") (name "CV2") (class "Default")
      (node (ref "JP1") (pin "4") (pinfunction "4_4") (pintype "passive"))
      (node (ref "R1") (pin "1") (pinfunction "1_1") (pintype "passive"))
    )
    (net (code "35") (name "CV3") (class "Default")
      (node (ref "JP1") (pin "2") (pinfunction "2_2") (pintype "passive"))
      (node (ref "R16") (pin "1") (pinfunction "1_1") (pintype "passive"))
    )
    (net (code "36") (name "CV4") (class "Default")
      (node (ref "JP1") (pin "1") (pinfunction "1_1") (pintype "passive"))
      (node (ref "R9") (pin "1") (pinfunction "1_1") (pintype "passive"))
    )
    (net (code "37") (name "ENC1A") (class "Default")
      (node (ref "JP6") (pin "11") (pinfunction "11_11") (pintype "passive"))
      (node (ref "U$2") (pin "19") (pinfunction "TIM4CH1_19") (pintype "bidirectional"))
    )
    (net (code "38") (name "ENC1B") (class "Default")
      (node (ref "JP6") (pin "12") (pinfunction "12_12") (pintype "passive"))
      (node (ref "U$2") (pin "20") (pinfunction "TIM4CH2_20") (pintype "bidirectional"))
    )
    (net (code "39") (name "ENC1SW") (class "Default")
      (node (ref "JP6") (pin "10") (pinfunction "10_10") (pintype "passive"))
      (node (ref "U$2") (pin "3") (pinfunction "EXTI8_3") (pintype "bidirectional"))
    )
    (net (code "40") (name "ENC2A") (class "Default")
      (node (ref "JP7") (pin "11") (pinfunction "11_11") (pintype "passive"))
      (node (ref "U$2") (pin "21") (pinfunction "TIM5CH1_21") (pintype "bidirectional"))
    )
    (net (code "41") (name "ENC2B") (class "Default")
      (node (ref "JP7") (pin "12") (pinfunction "12_12") (pintype "passive"))
      (node (ref "U$2") (pin "22") (pinfunction "TIM5CH2_22") (pintype "bidirectional"))
    )
    (net (code "42") (name "ENC2SW") (class "Default")
      (node (ref "JP7") (pin "10") (pinfunction "10_10") (pintype "passive"))
      (node (ref "U$2") (pin "7") (pinfunction "EXTI2_7") (pintype "bidirectional"))
    )
    (net (code "43") (name "ENC3A") (class "Default")
      (node (ref "JP8") (pin "11") (pinfunction "11_11") (pintype "passive"))
      (node (ref "U$2") (pin "23") (pinfunction "TIM8CH1_23") (pintype "bidirectional"))
    )
    (net (code "44") (name "ENC3B") (class "Default")
      (node (ref "JP8") (pin "12") (pinfunction "12_12") (pintype "passive"))
      (node (ref "U$2") (pin "24") (pinfunction "TIM8CH2_24") (pintype "bidirectional"))
    )
    (net (code "45") (name "ENC3SW") (class "Default")
      (node (ref "JP8") (pin "10") (pinfunction "10_10") (pintype "passive"))
      (node (ref "U$2") (pin "9") (pinfunction "EXTI0_9") (pintype "bidirectional"))
    )
    (net (code "46") (name "EXT_RX") (class "Default")
      (node (ref "BUS") (pin "P1") (pinfunction "-1_P1") (pintype "bidirectional"))
      (node (ref "U$2") (pin "82") (pinfunction "USART3_RX_82") (pintype "bidirectional"))
    )
    (net (code "47") (name "EXT_SCL") (class "Default")
      (node (ref "I2C") (pin "2") (pinfunction "2_2") (pintype "passive"))
      (node (ref "R108") (pin "2") (pinfunction "2_2") (pintype "passive"))
      (node (ref "U$2") (pin "73") (pinfunction "I2C_SCL_73") (pintype "bidirectional"))
    )
    (net (code "48") (name "EXT_SDA") (class "Default")
      (node (ref "I2C") (pin "3") (pinfunction "3_3") (pintype "passive"))
      (node (ref "R109") (pin "2") (pinfunction "2_2") (pintype "passive"))
      (node (ref "U$2") (pin "74") (pinfunction "I2C_SDA_74") (pintype "bidirectional"))
    )
    (net (code "49") (name "EXT_TX") (class "Default")
      (node (ref "BUS") (pin "P3") (pinfunction "-3_P3") (pintype "bidirectional"))
      (node (ref "U$2") (pin "84") (pinfunction "USART3_TX_84") (pintype "bidirectional"))
    )
    (net (code "50") (name "GND") (class "Default")
      (node (ref "BUS") (pin "P2") (pinfunction "-2_P2") (pintype "bidirectional"))
      (node (ref "C11") (pin "2") (pinfunction "2_2") (pintype "passive"))
      (node (ref "C12") (pin "1") (pinfunction "1_1") (pintype "passive"))
      (node (ref "C13") (pin "1") (pinfunction "1_1") (pintype "passive"))
      (node (ref "C15") (pin "2") (pinfunction "2_2") (pintype "passive"))
      (node (ref "C16") (pin "2") (pinfunction "2_2") (pintype "passive"))
      (node (ref "C18") (pin "2") (pinfunction "2_2") (pintype "passive"))
      (node (ref "C2") (pin "2") (pinfunction "2_2") (pintype "passive"))
      (node (ref "C20") (pin "2") (pinfunction "2_2") (pintype "passive"))
      (node (ref "C21") (pin "2") (pinfunction "2_2") (pintype "passive"))
      (node (ref "C23") (pin "2") (pinfunction "2_2") (pintype "passive"))
      (node (ref "C24") (pin "2") (pinfunction "2_2") (pintype "passive"))
      (node (ref "C26") (pin "2") (pinfunction "2_2") (pintype "passive"))
      (node (ref "C27") (pin "2") (pinfunction "2_2") (pintype "passive"))
      (node (ref "C29") (pin "2") (pinfunction "2_2") (pintype "passive"))
      (node (ref "C3") (pin "2") (pinfunction "2_2") (pintype "passive"))
      (node (ref "C30") (pin "2") (pinfunction "2_2") (pintype "passive"))
      (node (ref "C31") (pin "2") (pinfunction "2_2") (pintype "passive"))
      (node (ref "C33") (pin "2") (pinfunction "2_2") (pintype "passive"))
      (node (ref "C35") (pin "2") (pinfunction "2_2") (pintype "passive"))
      (node (ref "C37") (pin "1") (pinfunction "1_1") (pintype "passive"))
      (node (ref "C38") (pin "2") (pinfunction "2_2") (pintype "passive"))
      (node (ref "C39") (pin "1") (pinfunction "1_1") (pintype "passive"))
      (node (ref "C42") (pin "1") (pinfunction "1_1") (pintype "passive"))
      (node (ref "C43") (pin "2") (pinfunction "2_2") (pintype "passive"))
      (node (ref "C44") (pin "1") (pinfunction "1_1") (pintype "passive"))
      (node (ref "C47") (pin "1") (pinfunction "1_1") (pintype "passive"))
      (node (ref "C48") (pin "2") (pinfunction "2_2") (pintype "passive"))
      (node (ref "C49") (pin "1") (pinfunction "1_1") (pintype "passive"))
      (node (ref "C57") (pin "2") (pinfunction "2_2") (pintype "passive"))
      (node (ref "C58") (pin "2") (pinfunction "2_2") (pintype "passive"))
      (node (ref "C59") (pin "-") (pinfunction "-_-") (pintype "passive"))
      (node (ref "C60") (pin "+") (pinfunction "+_+") (pintype "passive"))
      (node (ref "C61") (pin "-") (pinfunction "-_-") (pintype "passive"))
      (node (ref "C8") (pin "2") (pinfunction "2_2") (pintype "passive"))
      (node (ref "D1") (pin "1") (pinfunction "A1_1") (pintype "passive"))
      (node (ref "D2") (pin "1") (pinfunction "A1_1") (pintype "passive"))
      (node (ref "D3") (pin "1") (pinfunction "A1_1") (pintype "passive"))
      (node (ref "D4") (pin "1") (pinfunction "A1_1") (pintype "passive"))
      (node (ref "I2C") (pin "1") (pinfunction "1_1") (pintype "passive"))
      (node (ref "IC1") (pin "10") (pinfunction "+IN_10") (pintype "input"))
      (node (ref "IC1") (pin "12") (pinfunction "+IN_12") (pintype "input"))
      (node (ref "IC1") (pin "3") (pinfunction "+IN_3") (pintype "input"))
      (node (ref "IC1") (pin "5") (pinfunction "+IN_5") (pintype "input"))
      (node (ref "IC3") (pin "3") (pinfunction "+IN_3") (pintype "input"))
      (node (ref "IC4") (pin "3") (pinfunction "+IN_3") (pintype "input"))
      (node (ref "IC4") (pin "5") (pinfunction "+IN_5") (pintype "input"))
      (node (ref "IC5") (pin "3") (pinfunction "+IN_3") (pintype "input"))
      (node (ref "IC5") (pin "5") (pinfunction "+IN_5") (pintype "input"))
      (node (ref "IC6") (pin "3") (pinfunction "+IN_3") (pintype "input"))
      (node (ref "IC6") (pin "5") (pinfunction "+IN_5") (pintype "input"))
      (node (ref "JP1") (pin "3") (pinfunction "3_3") (pintype "passive"))
      (node (ref "JP2") (pin "6") (pinfunction "6_6") (pintype "passive"))
      (node (ref "JP3") (pin "3") (pinfunction "3_3") (pintype "passive"))
      (node (ref "JP4") (pin "6") (pinfunction "6_6") (pintype "passive"))
      (node (ref "JP5") (pin "1") (pinfunction "1_1") (pintype "passive"))
      (node (ref "JP5") (pin "12") (pinfunction "12_12") (pintype "passive"))
      (node (ref "JP6") (pin "1") (pinfunction "1_1") (pintype "passive"))
      (node (ref "JP7") (pin "1") (pinfunction "1_1") (pintype "passive"))
      (node (ref "JP8") (pin "1") (pinfunction "1_1") (pintype "passive"))
      (node (ref "PWR") (pin "3") (pinfunction "3_3") (pintype "passive"))
      (node (ref "PWR") (pin "4") (pinfunction "4_4") (pintype "passive"))
      (node (ref "PWR") (pin "5") (pinfunction "5_5") (pintype "passive"))
      (node (ref "PWR") (pin "6") (pinfunction "6_6") (pintype "passive"))
      (node (ref "PWR") (pin "7") (pinfunction "7_7") (pintype "passive"))
      (node (ref "PWR") (pin "8") (pinfunction "8_8") (pintype "passive"))
      (node (ref "Q1") (pin "2") (pinfunction "E_2") (pintype "passive"))
      (node (ref "Q2") (pin "2") (pinfunction "E_2") (pintype "passive"))
      (node (ref "Q3") (pin "2") (pinfunction "E_2") (pintype "passive"))
      (node (ref "R102") (pin "2") (pinfunction "2_2") (pintype "passive"))
      (node (ref "R104") (pin "2") (pinfunction "2_2") (pintype "passive"))
      (node (ref "R21") (pin "2") (pinfunction "2_2") (pintype "passive"))
      (node (ref "R29") (pin "2") (pinfunction "2_2") (pintype "passive"))
      (node (ref "R63") (pin "2") (pinfunction "2_2") (pintype "passive"))
      (node (ref "R69") (pin "2") (pinfunction "2_2") (pintype "passive"))
      (node (ref "R74") (pin "2") (pinfunction "2_2") (pintype "passive"))
      (node (ref "R80") (pin "2") (pinfunction "2_2") (pintype "passive"))
      (node (ref "R82") (pin "2") (pinfunction "2_2") (pintype "passive"))
      (node (ref "R91") (pin "2") (pinfunction "2_2") (pintype "passive"))
      (node (ref "R93") (pin "2") (pinfunction "2_2") (pintype "passive"))
      (node (ref "U$2") (pin "15") (pinfunction "GND_15") (pintype "bidirectional"))
      (node (ref "U$2") (pin "16") (pinfunction "GND_16") (pintype "bidirectional"))
      (node (ref "U$2") (pin "33") (pinfunction "AGND_33") (pintype "bidirectional"))
      (node (ref "U$2") (pin "36") (pinfunction "AIN1N_36") (pintype "bidirectional"))
      (node (ref "U$2") (pin "38") (pinfunction "AIN2N_38") (pintype "bidirectional"))
      (node (ref "U$2") (pin "40") (pinfunction "AIN3N_40") (pintype "bidirectional"))
      (node (ref "U$2") (pin "42") (pinfunction "AIN4N_42") (pintype "bidirectional"))
      (node (ref "U$2") (pin "44") (pinfunction "AIN5N_44") (pintype "bidirectional"))
      (node (ref "U$2") (pin "46") (pinfunction "AIN6N_46") (pintype "bidirectional"))
      (node (ref "U$2") (pin "47") (pinfunction "AGND_47") (pintype "bidirectional"))
      (node (ref "U$2") (pin "48") (pinfunction "AGND_48") (pintype "bidirectional"))
      (node (ref "U$2") (pin "49") (pinfunction "AGND_49") (pintype "bidirectional"))
      (node (ref "U$2") (pin "50") (pinfunction "AGND_50") (pintype "bidirectional"))
      (node (ref "U$2") (pin "67") (pinfunction "AGND_67") (pintype "bidirectional"))
      (node (ref "U$2") (pin "71") (pinfunction "AGND_71") (pintype "bidirectional"))
      (node (ref "U$2") (pin "72") (pinfunction "AGND_72") (pintype "bidirectional"))
      (node (ref "U$2") (pin "85") (pinfunction "GND_85") (pintype "bidirectional"))
      (node (ref "U$2") (pin "86") (pinfunction "GND_86") (pintype "bidirectional"))
      (node (ref "U1") (pin "2") (pinfunction "GND_2") (pintype "power_in"))
    )
    (net (code "51") (name "IN1") (class "Default")
      (node (ref "JP6") (pin "4") (pinfunction "4_4") (pintype "passive"))
      (node (ref "R34") (pin "2") (pinfunction "2_2") (pintype "passive"))
    )
    (net (code "52") (name "IN2") (class "Default")
      (node (ref "JP6") (pin "5") (pinfunction "5_5") (pintype "passive"))
      (node (ref "R38") (pin "2") (pinfunction "2_2") (pintype "passive"))
    )
    (net (code "53") (name "IN3") (class "Default")
      (node (ref "JP7") (pin "4") (pinfunction "4_4") (pintype "passive"))
      (node (ref "R43") (pin "2") (pinfunction "2_2") (pintype "passive"))
    )
    (net (code "54") (name "IN4") (class "Default")
      (node (ref "JP7") (pin "5") (pinfunction "5_5") (pintype "passive"))
      (node (ref "R47") (pin "2") (pinfunction "2_2") (pintype "passive"))
    )
    (net (code "55") (name "IN5") (class "Default")
      (node (ref "JP8") (pin "4") (pinfunction "4_4") (pintype "passive"))
      (node (ref "R54") (pin "2") (pinfunction "2_2") (pintype "passive"))
    )
    (net (code "56") (name "IN6") (class "Default")
      (node (ref "JP8") (pin "5") (pinfunction "5_5") (pintype "passive"))
      (node (ref "R55") (pin "2") (pinfunction "2_2") (pintype "passive"))
    )
    (net (code "57") (name "LEDSW4") (class "Default")
      (node (ref "R41") (pin "1") (pinfunction "1_1") (pintype "passive"))
      (node (ref "U$2") (pin "5") (pinfunction "EXTI4_5") (pintype "bidirectional"))
    )
    (net (code "58") (name "LEDSW4A") (class "Default")
      (node (ref "JP6") (pin "9") (pinfunction "9_9") (pintype "passive"))
      (node (ref "R41") (pin "2") (pinfunction "2_2") (pintype "passive"))
    )
    (net (code "59") (name "LEDSW4C") (class "Default")
      (node (ref "JP6") (pin "8") (pinfunction "8_8") (pintype "passive"))
      (node (ref "U$2") (pin "13") (pinfunction "TIM2CH1_13") (pintype "bidirectional"))
    )
    (net (code "60") (name "LEDSW5") (class "Default")
      (node (ref "R50") (pin "1") (pinfunction "1_1") (pintype "passive"))
      (node (ref "U$2") (pin "28") (pinfunction "ADC6_28") (pintype "bidirectional"))
    )
    (net (code "61") (name "LEDSW5A") (class "Default")
      (node (ref "JP7") (pin "9") (pinfunction "9_9") (pintype "passive"))
      (node (ref "R50") (pin "2") (pinfunction "2_2") (pintype "passive"))
    )
    (net (code "62") (name "LEDSW5C") (class "Default")
      (node (ref "JP7") (pin "8") (pinfunction "8_8") (pintype "passive"))
      (node (ref "U$2") (pin "30") (pinfunction "ADC7_30") (pintype "bidirectional"))
    )
    (net (code "63") (name "LEDSW6") (class "Default")
      (node (ref "R59") (pin "1") (pinfunction "1_1") (pintype "passive"))
      (node (ref "U$2") (pin "10") (pinfunction "EXTI1_10") (pintype "bidirectional"))
    )
    (net (code "64") (name "LEDSW6A") (class "Default")
      (node (ref "JP8") (pin "9") (pinfunction "9_9") (pintype "passive"))
      (node (ref "R59") (pin "2") (pinfunction "2_2") (pintype "passive"))
    )
    (net (code "65") (name "LEDSW6C") (class "Default")
      (node (ref "JP8") (pin "8") (pinfunction "8_8") (pintype "passive"))
      (node (ref "U$2") (pin "14") (pinfunction "TIM2CH2_14") (pintype "bidirectional"))
    )
    (net (code "66") (name "Net-(C7-Pad1)") (class "Default")
      (node (ref "C7") (pin "1") (pinfunction "1_1") (pintype "passive"))
      (node (ref "R17") (pin "1") (pinfunction "1_1") (pintype "passive"))
      (node (ref "R18") (pin "2") (pinfunction "2_2") (pintype "passive"))
      (node (ref "R19") (pin "2") (pinfunction "2_2") (pintype "passive"))
    )
    (net (code "67") (name "Net-(C7-Pad2)") (class "Default")
      (node (ref "C7") (pin "2") (pinfunction "2_2") (pintype "passive"))
      (node (ref "R20") (pin "2") (pinfunction "2_2") (pintype "passive"))
      (node (ref "R21") (pin "1") (pinfunction "1_1") (pintype "passive"))
      (node (ref "R22") (pin "1") (pinfunction "1_1") (pintype "passive"))
    )
    (net (code "68") (name "Net-(C14-Pad1)") (class "Default")
      (node (ref "C14") (pin "1") (pinfunction "1_1") (pintype "passive"))
      (node (ref "R25") (pin "2") (pinfunction "2_2") (pintype "passive"))
      (node (ref "R26") (pin "1") (pinfunction "1_1") (pintype "passive"))
      (node (ref "R27") (pin "2") (pinfunction "2_2") (pintype "passive"))
    )
    (net (code "69") (name "Net-(C14-Pad2)") (class "Default")
      (node (ref "C14") (pin "2") (pinfunction "2_2") (pintype "passive"))
      (node (ref "R28") (pin "2") (pinfunction "2_2") (pintype "passive"))
      (node (ref "R29") (pin "1") (pinfunction "1_1") (pintype "passive"))
      (node (ref "R30") (pin "1") (pinfunction "1_1") (pintype "passive"))
    )
    (net (code "70") (name "Net-(C51-Pad1)") (class "Default")
      (node (ref "C51") (pin "1") (pinfunction "1_1") (pintype "passive"))
      (node (ref "R75") (pin "2") (pinfunction "2_2") (pintype "passive"))
      (node (ref "R76") (pin "1") (pinfunction "1_1") (pintype "passive"))
      (node (ref "R77") (pin "2") (pinfunction "2_2") (pintype "passive"))
    )
    (net (code "71") (name "Net-(C51-Pad2)") (class "Default")
      (node (ref "C51") (pin "2") (pinfunction "2_2") (pintype "passive"))
      (node (ref "R78") (pin "1") (pinfunction "1_1") (pintype "passive"))
      (node (ref "R79") (pin "2") (pinfunction "2_2") (pintype "passive"))
      (node (ref "R80") (pin "1") (pinfunction "1_1") (pintype "passive"))
    )
    (net (code "72") (name "Net-(C52-Pad1)") (class "Default")
      (node (ref "C52") (pin "1") (pinfunction "1_1") (pintype "passive"))
      (node (ref "R83") (pin "2") (pinfunction "2_2") (pintype "passive"))
      (node (ref "R85") (pin "2") (pinfunction "2_2") (pintype "passive"))
      (node (ref "R86") (pin "1") (pinfunction "1_1") (pintype "passive"))
    )
    (net (code "73") (name "Net-(C52-Pad2)") (class "Default")
      (node (ref "C52") (pin "2") (pinfunction "2_2") (pintype "passive"))
      (node (ref "R81") (pin "2") (pinfunction "2_2") (pintype "passive"))
      (node (ref "R82") (pin "1") (pinfunction "1_1") (pintype "passive"))
      (node (ref "R84") (pin "1") (pinfunction "1_1") (pintype "passive"))
    )
    (net (code "74") (name "Net-(C53-Pad1)") (class "Default")
      (node (ref "C53") (pin "1") (pinfunction "1_1") (pintype "passive"))
      (node (ref "R65") (pin "2") (pinfunction "2_2") (pintype "passive"))
      (node (ref "R87") (pin "2") (pinfunction "2_2") (pintype "passive"))
      (node (ref "R88") (pin "1") (pinfunction "1_1") (pintype "passive"))
    )
    (net (code "75") (name "Net-(C53-Pad2)") (class "Default")
      (node (ref "C53") (pin "2") (pinfunction "2_2") (pintype "passive"))
      (node (ref "R89") (pin "1") (pinfunction "1_1") (pintype "passive"))
      (node (ref "R90") (pin "2") (pinfunction "2_2") (pintype "passive"))
      (node (ref "R91") (pin "1") (pinfunction "1_1") (pintype "passive"))
    )
    (net (code "76") (name "Net-(C54-Pad1)") (class "Default")
      (node (ref "C54") (pin "1") (pinfunction "1_1") (pintype "passive"))
      (node (ref "R66") (pin "2") (pinfunction "2_2") (pintype "passive"))
      (node (ref "R95") (pin "2") (pinfunction "2_2") (pintype "passive"))
      (node (ref "R96") (pin "1") (pinfunction "1_1") (pintype "passive"))
    )
    (net (code "77") (name "Net-(C54-Pad2)") (class "Default")
      (node (ref "C54") (pin "2") (pinfunction "2_2") (pintype "passive"))
      (node (ref "R92") (pin "2") (pinfunction "2_2") (pintype "passive"))
      (node (ref "R93") (pin "1") (pinfunction "1_1") (pintype "passive"))
      (node (ref "R94") (pin "1") (pinfunction "1_1") (pintype "passive"))
    )
    (net (code "78") (name "Net-(C55-Pad1)") (class "Default")
      (node (ref "C55") (pin "1") (pinfunction "1_1") (pintype "passive"))
      (node (ref "R97") (pin "1") (pinfunction "1_1") (pintype "passive"))
      (node (ref "R98") (pin "2") (pinfunction "2_2") (pintype "passive"))
      (node (ref "R99") (pin "2") (pinfunction "2_2") (pintype "passive"))
    )
    (net (code "79") (name "Net-(C55-Pad2)") (class "Default")
      (node (ref "C55") (pin "2") (pinfunction "2_2") (pintype "passive"))
      (node (ref "R100") (pin "1") (pinfunction "1_1") (pintype "passive"))
      (node (ref "R101") (pin "2") (pinfunction "2_2") (pintype "passive"))
      (node (ref "R102") (pin "1") (pinfunction "1_1") (pintype "passive"))
    )
    (net (code "80") (name "Net-(C56-Pad1)") (class "Default")
      (node (ref "C56") (pin "1") (pinfunction "1_1") (pintype "passive"))
      (node (ref "R106") (pin "2") (pinfunction "2_2") (pintype "passive"))
      (node (ref "R107") (pin "1") (pinfunction "1_1") (pintype "passive"))
      (node (ref "R71") (pin "2") (pinfunction "2_2") (pintype "passive"))
    )
    (net (code "81") (name "Net-(C56-Pad2)") (class "Default")
      (node (ref "C56") (pin "2") (pinfunction "2_2") (pintype "passive"))
      (node (ref "R103") (pin "2") (pinfunction "2_2") (pintype "passive"))
      (node (ref "R104") (pin "1") (pinfunction "1_1") (pintype "passive"))
      (node (ref "R105") (pin "1") (pinfunction "1_1") (pintype "passive"))
    )
    (net (code "82") (name "Net-(D1-C1A2)") (class "Default")
      (node (ref "D1") (pin "3") (pinfunction "C1A2_3") (pintype "passive"))
      (node (ref "R2") (pin "2") (pinfunction "2_2") (pintype "passive"))
      (node (ref "R3") (pin "1") (pinfunction "1_1") (pintype "passive"))
    )
    (net (code "83") (name "Net-(D2-C1A2)") (class "Default")
      (node (ref "D2") (pin "3") (pinfunction "C1A2_3") (pintype "passive"))
      (node (ref "R7") (pin "2") (pinfunction "2_2") (pintype "passive"))
      (node (ref "R8") (pin "1") (pinfunction "1_1") (pintype "passive"))
    )
    (net (code "84") (name "Net-(D3-C1A2)") (class "Default")
      (node (ref "D3") (pin "3") (pinfunction "C1A2_3") (pintype "passive"))
      (node (ref "R10") (pin "1") (pinfunction "1_1") (pintype "passive"))
      (node (ref "R11") (pin "2") (pinfunction "2_2") (pintype "passive"))
    )
    (net (code "85") (name "Net-(D4-C1A2)") (class "Default")
      (node (ref "D4") (pin "3") (pinfunction "C1A2_3") (pintype "passive"))
      (node (ref "R14") (pin "1") (pinfunction "1_1") (pintype "passive"))
      (node (ref "R15") (pin "2") (pinfunction "2_2") (pintype "passive"))
    )
    (net (code "86") (name "Net-(D5-PadA)") (class "Default")
      (node (ref "D5") (pin "A") (pinfunction "A_A") (pintype "passive"))
      (node (ref "PWR") (pin "1") (pinfunction "1_1") (pintype "passive"))
      (node (ref "PWR") (pin "2") (pinfunction "2_2") (pintype "passive"))
    )
    (net (code "87") (name "Net-(D6-PadC)") (class "Default")
      (node (ref "D6") (pin "C") (pinfunction "C_C") (pintype "passive"))
      (node (ref "PWR") (pin "10") (pinfunction "10_10") (pintype "passive"))
      (node (ref "PWR") (pin "9") (pinfunction "9_9") (pintype "passive"))
    )
    (net (code "88") (name "Net-(IC1A--IN)") (class "Default")
      (node (ref "C1") (pin "1") (pinfunction "1_1") (pintype "passive"))
      (node (ref "IC1") (pin "2") (pinfunction "-IN_2") (pintype "input"))
      (node (ref "R4") (pin "2") (pinfunction "2_2") (pintype "passive"))
      (node (ref "R5") (pin "1") (pinfunction "1_1") (pintype "passive"))
    )
    (net (code "89") (name "Net-(IC1A-OUT)") (class "Default")
      (node (ref "C1") (pin "2") (pinfunction "2_2") (pintype "passive"))
      (node (ref "IC1") (pin "1") (pinfunction "OUT_1") (pintype "output"))
      (node (ref "R3") (pin "2") (pinfunction "2_2") (pintype "passive"))
      (node (ref "R5") (pin "2") (pinfunction "2_2") (pintype "passive"))
    )
    (net (code "90") (name "Net-(IC1B--IN)") (class "Default")
      (node (ref "C5") (pin "1") (pinfunction "1_1") (pintype "passive"))
      (node (ref "IC1") (pin "6") (pinfunction "-IN_6") (pintype "input"))
      (node (ref "R1") (pin "2") (pinfunction "2_2") (pintype "passive"))
      (node (ref "R12") (pin "1") (pinfunction "1_1") (pintype "passive"))
    )
    (net (code "91") (name "Net-(IC1B-OUT)") (class "Default")
      (node (ref "C5") (pin "2") (pinfunction "2_2") (pintype "passive"))
      (node (ref "IC1") (pin "7") (pinfunction "OUT_7") (pintype "output"))
      (node (ref "R10") (pin "2") (pinfunction "2_2") (pintype "passive"))
      (node (ref "R12") (pin "2") (pinfunction "2_2") (pintype "passive"))
    )
    (net (code "92") (name "Net-(IC1C--IN)") (class "Default")
      (node (ref "C6") (pin "1") (pinfunction "1_1") (pintype "passive"))
      (node (ref "IC1") (pin "9") (pinfunction "-IN_9") (pintype "input"))
      (node (ref "R13") (pin "1") (pinfunction "1_1") (pintype "passive"))
      (node (ref "R16") (pin "2") (pinfunction "2_2") (pintype "passive"))
    )
    (net (code "93") (name "Net-(IC1C-OUT)") (class "Default")
      (node (ref "C6") (pin "2") (pinfunction "2_2") (pintype "passive"))
      (node (ref "IC1") (pin "8") (pinfunction "OUT_8") (pintype "output"))
      (node (ref "R13") (pin "2") (pinfunction "2_2") (pintype "passive"))
      (node (ref "R14") (pin "2") (pinfunction "2_2") (pintype "passive"))
    )
    (net (code "94") (name "Net-(IC1D--IN)") (class "Default")
      (node (ref "C4") (pin "1") (pinfunction "1_1") (pintype "passive"))
      (node (ref "IC1") (pin "13") (pinfunction "-IN_13") (pintype "input"))
      (node (ref "R6") (pin "1") (pinfunction "1_1") (pintype "passive"))
      (node (ref "R9") (pin "2") (pinfunction "2_2") (pintype "passive"))
    )
    (net (code "95") (name "Net-(IC1D-OUT)") (class "Default")
      (node (ref "C4") (pin "2") (pinfunction "2_2") (pintype "passive"))
      (node (ref "IC1") (pin "14") (pinfunction "OUT_14") (pintype "output"))
      (node (ref "R6") (pin "2") (pinfunction "2_2") (pintype "passive"))
      (node (ref "R8") (pin "2") (pinfunction "2_2") (pintype "passive"))
    )
    (net (code "96") (name "Net-(IC2A-+IN)") (class "Default")
      (node (ref "C13") (pin "2") (pinfunction "2_2") (pintype "passive"))
      (node (ref "IC2") (pin "3") (pinfunction "+IN_3") (pintype "input"))
      (node (ref "R28") (pin "1") (pinfunction "1_1") (pintype "passive"))
    )
    (net (code "97") (name "Net-(IC2A--IN)") (class "Default")
      (node (ref "C9") (pin "1") (pinfunction "1_1") (pintype "passive"))
      (node (ref "IC2") (pin "2") (pinfunction "-IN_2") (pintype "input"))
      (node (ref "R27") (pin "1") (pinfunction "1_1") (pintype "passive"))
    )
    (net (code "98") (name "Net-(IC2A-OUT)") (class "Default")
      (node (ref "C9") (pin "2") (pinfunction "2_2") (pintype "passive"))
      (node (ref "IC2") (pin "1") (pinfunction "OUT_1") (pintype "output"))
      (node (ref "R23") (pin "2") (pinfunction "2_2") (pintype "passive"))
      (node (ref "R25") (pin "1") (pinfunction "1_1") (pintype "passive"))
    )
    (net (code "99") (name "Net-(IC2B-+IN)") (class "Default")
      (node (ref "C12") (pin "2") (pinfunction "2_2") (pintype "passive"))
      (node (ref "IC2") (pin "5") (pinfunction "+IN_5") (pintype "input"))
      (node (ref "R20") (pin "1") (pinfunction "1_1") (pintype "passive"))
    )
    (net (code "100") (name "Net-(IC2B--IN)") (class "Default")
      (node (ref "C10") (pin "1") (pinfunction "1_1") (pintype "passive"))
      (node (ref "IC2") (pin "6") (pinfunction "-IN_6") (pintype "input"))
      (node (ref "R19") (pin "1") (pinfunction "1_1") (pintype "passive"))
    )
    (net (code "101") (name "Net-(IC2B-OUT)") (class "Default")
      (node (ref "C10") (pin "2") (pinfunction "2_2") (pintype "passive"))
      (node (ref "IC2") (pin "7") (pinfunction "OUT_7") (pintype "output"))
      (node (ref "R18") (pin "1") (pinfunction "1_1") (pintype "passive"))
      (node (ref "R24") (pin "2") (pinfunction "2_2") (pintype "passive"))
    )
    (net (code "102") (name "Net-(IC3--IN)") (class "Default")
      (node (ref "IC3") (pin "4") (pinfunction "-IN_4") (pintype "input"))
      (node (ref "R31") (pin "1") (pinfunction "1_1") (pintype "passive"))
      (node (ref "R32") (pin "2") (pinfunction "2_2") (pintype "passive"))
    )
    (net (code "103") (name "Net-(IC4A--IN)") (class "Default")
      (node (ref "C22") (pin "1") (pinfunction "1_1") (pintype "passive"))
      (node (ref "IC4") (pin "2") (pinfunction "-IN_2") (pintype "input"))
      (node (ref "R37") (pin "1") (pinfunction "1_1") (pintype "passive"))
      (node (ref "R38") (pin "1") (pinfunction "1_1") (pintype "passive"))
      (node (ref "R39") (pin "2") (pinfunction "2_2") (pintype "passive"))
    )
    (net (code "104") (name "Net-(IC4A-OUT)") (class "Default")
      (node (ref "C22") (pin "2") (pinfunction "2_2") (pintype "passive"))
      (node (ref "IC4") (pin "1") (pinfunction "OUT_1") (pintype "output"))
      (node (ref "R39") (pin "1") (pinfunction "1_1") (pintype "passive"))
      (node (ref "R40") (pin "2") (pinfunction "2_2") (pintype "passive"))
    )
    (net (code "105") (name "Net-(IC4B--IN)") (class "Default")
      (node (ref "C19") (pin "1") (pinfunction "1_1") (pintype "passive"))
      (node (ref "IC4") (pin "6") (pinfunction "-IN_6") (pintype "input"))
      (node (ref "R34") (pin "1") (pinfunction "1_1") (pintype "passive"))
      (node (ref "R35") (pin "1") (pinfunction "1_1") (pintype "passive"))
      (node (ref "R36") (pin "2") (pinfunction "2_2") (pintype "passive"))
    )
    (net (code "106") (name "Net-(IC4B-OUT)") (class "Default")
      (node (ref "C19") (pin "2") (pinfunction "2_2") (pintype "passive"))
      (node (ref "IC4") (pin "7") (pinfunction "OUT_7") (pintype "output"))
      (node (ref "R33") (pin "2") (pinfunction "2_2") (pintype "passive"))
      (node (ref "R36") (pin "1") (pinfunction "1_1") (pintype "passive"))
    )
    (net (code "107") (name "Net-(IC4C-+IN)") (class "Default")
      (node (ref "C37") (pin "2") (pinfunction "2_2") (pintype "passive"))
      (node (ref "IC4") (pin "10") (pinfunction "+IN_10") (pintype "input"))
      (node (ref "R79") (pin "1") (pinfunction "1_1") (pintype "passive"))
    )
    (net (code "108") (name "Net-(IC4C--IN)") (class "Default")
      (node (ref "C36") (pin "1") (pinfunction "1_1") (pintype "passive"))
      (node (ref "IC4") (pin "9") (pinfunction "-IN_9") (pintype "input"))
      (node (ref "R77") (pin "1") (pinfunction "1_1") (pintype "passive"))
    )
    (net (code "109") (name "Net-(IC4C-OUT)") (class "Default")
      (node (ref "C36") (pin "2") (pinfunction "2_2") (pintype "passive"))
      (node (ref "IC4") (pin "8") (pinfunction "OUT_8") (pintype "output"))
      (node (ref "R60") (pin "2") (pinfunction "2_2") (pintype "passive"))
      (node (ref "R75") (pin "1") (pinfunction "1_1") (pintype "passive"))
    )
    (net (code "110") (name "Net-(IC4D-+IN)") (class "Default")
      (node (ref "C39") (pin "2") (pinfunction "2_2") (pintype "passive"))
      (node (ref "IC4") (pin "12") (pinfunction "+IN_12") (pintype "input"))
      (node (ref "R81") (pin "1") (pinfunction "1_1") (pintype "passive"))
    )
    (net (code "111") (name "Net-(IC4D--IN)") (class "Default")
      (node (ref "C40") (pin "1") (pinfunction "1_1") (pintype "passive"))
      (node (ref "IC4") (pin "13") (pinfunction "-IN_13") (pintype "input"))
      (node (ref "R83") (pin "1") (pinfunction "1_1") (pintype "passive"))
    )
    (net (code "112") (name "Net-(IC4D-OUT)") (class "Default")
      (node (ref "C40") (pin "2") (pinfunction "2_2") (pintype "passive"))
      (node (ref "IC4") (pin "14") (pinfunction "OUT_14") (pintype "output"))
      (node (ref "R61") (pin "2") (pinfunction "2_2") (pintype "passive"))
      (node (ref "R85") (pin "1") (pinfunction "1_1") (pintype "passive"))
    )
    (net (code "113") (name "Net-(IC5A--IN)") (class "Default")
      (node (ref "C28") (pin "1") (pinfunction "1_1") (pintype "passive"))
      (node (ref "IC5") (pin "2") (pinfunction "-IN_2") (pintype "input"))
      (node (ref "R46") (pin "1") (pinfunction "1_1") (pintype "passive"))
      (node (ref "R47") (pin "1") (pinfunction "1_1") (pintype "passive"))
      (node (ref "R48") (pin "2") (pinfunction "2_2") (pintype "passive"))
    )
    (net (code "114") (name "Net-(IC5A-OUT)") (class "Default")
      (node (ref "C28") (pin "2") (pinfunction "2_2") (pintype "passive"))
      (node (ref "IC5") (pin "1") (pinfunction "OUT_1") (pintype "output"))
      (node (ref "R48") (pin "1") (pinfunction "1_1") (pintype "passive"))
      (node (ref "R49") (pin "2") (pinfunction "2_2") (pintype "passive"))
    )
    (net (code "115") (name "Net-(IC5B--IN)") (class "Default")
      (node (ref "C25") (pin "1") (pinfunction "1_1") (pintype "passive"))
      (node (ref "IC5") (pin "6") (pinfunction "-IN_6") (pintype "input"))
      (node (ref "R43") (pin "1") (pinfunction "1_1") (pintype "passive"))
      (node (ref "R44") (pin "1") (pinfunction "1_1") (pintype "passive"))
      (node (ref "R45") (pin "2") (pinfunction "2_2") (pintype "passive"))
    )
    (net (code "116") (name "Net-(IC5B-OUT)") (class "Default")
      (node (ref "C25") (pin "2") (pinfunction "2_2") (pintype "passive"))
      (node (ref "IC5") (pin "7") (pinfunction "OUT_7") (pintype "output"))
      (node (ref "R42") (pin "2") (pinfunction "2_2") (pintype "passive"))
      (node (ref "R45") (pin "1") (pinfunction "1_1") (pintype "passive"))
    )
    (net (code "117") (name "Net-(IC5C-+IN)") (class "Default")
      (node (ref "C42") (pin "2") (pinfunction "2_2") (pintype "passive"))
      (node (ref "IC5") (pin "10") (pinfunction "+IN_10") (pintype "input"))
      (node (ref "R90") (pin "1") (pinfunction "1_1") (pintype "passive"))
    )
    (net (code "118") (name "Net-(IC5C--IN)") (class "Default")
      (node (ref "C41") (pin "1") (pinfunction "1_1") (pintype "passive"))
      (node (ref "IC5") (pin "9") (pinfunction "-IN_9") (pintype "input"))
      (node (ref "R65") (pin "1") (pinfunction "1_1") (pintype "passive"))
    )
    (net (code "119") (name "Net-(IC5C-OUT)") (class "Default")
      (node (ref "C41") (pin "2") (pinfunction "2_2") (pintype "passive"))
      (node (ref "IC5") (pin "8") (pinfunction "OUT_8") (pintype "output"))
      (node (ref "R64") (pin "2") (pinfunction "2_2") (pintype "passive"))
      (node (ref "R87") (pin "1") (pinfunction "1_1") (pintype "passive"))
    )
    (net (code "120") (name "Net-(IC5D-+IN)") (class "Default")
      (node (ref "C44") (pin "2") (pinfunction "2_2") (pintype "passive"))
      (node (ref "IC5") (pin "12") (pinfunction "+IN_12") (pintype "input"))
      (node (ref "R92") (pin "1") (pinfunction "1_1") (pintype "passive"))
    )
    (net (code "121") (name "Net-(IC5D--IN)") (class "Default")
      (node (ref "C45") (pin "1") (pinfunction "1_1") (pintype "passive"))
      (node (ref "IC5") (pin "13") (pinfunction "-IN_13") (pintype "input"))
      (node (ref "R66") (pin "1") (pinfunction "1_1") (pintype "passive"))
    )
    (net (code "122") (name "Net-(IC5D-OUT)") (class "Default")
      (node (ref "C45") (pin "2") (pinfunction "2_2") (pintype "passive"))
      (node (ref "IC5") (pin "14") (pinfunction "OUT_14") (pintype "output"))
      (node (ref "R67") (pin "2") (pinfunction "2_2") (pintype "passive"))
      (node (ref "R95") (pin "1") (pinfunction "1_1") (pintype "passive"))
    )
    (net (code "123") (name "Net-(IC6A--IN)") (class "Default")
      (node (ref "C34") (pin "1") (pinfunction "1_1") (pintype "passive"))
      (node (ref "IC6") (pin "2") (pinfunction "-IN_2") (pintype "input"))
      (node (ref "R55") (pin "1") (pinfunction "1_1") (pintype "passive"))
      (node (ref "R56") (pin "1") (pinfunction "1_1") (pintype "passive"))
      (node (ref "R57") (pin "2") (pinfunction "2_2") (pintype "passive"))
    )
    (net (code "124") (name "Net-(IC6A-OUT)") (class "Default")
      (node (ref "C34") (pin "2") (pinfunction "2_2") (pintype "passive"))
      (node (ref "IC6") (pin "1") (pinfunction "OUT_1") (pintype "output"))
      (node (ref "R57") (pin "1") (pinfunction "1_1") (pintype "passive"))
      (node (ref "R58") (pin "2") (pinfunction "2_2") (pintype "passive"))
    )
    (net (code "125") (name "Net-(IC6B--IN)") (class "Default")
      (node (ref "C32") (pin "1") (pinfunction "1_1") (pintype "passive"))
      (node (ref "IC6") (pin "6") (pinfunction "-IN_6") (pintype "input"))
      (node (ref "R52") (pin "1") (pinfunction "1_1") (pintype "passive"))
      (node (ref "R53") (pin "2") (pinfunction "2_2") (pintype "passive"))
      (node (ref "R54") (pin "1") (pinfunction "1_1") (pintype "passive"))
    )
    (net (code "126") (name "Net-(IC6B-OUT)") (class "Default")
      (node (ref "C32") (pin "2") (pinfunction "2_2") (pintype "passive"))
      (node (ref "IC6") (pin "7") (pinfunction "OUT_7") (pintype "output"))
      (node (ref "R51") (pin "2") (pinfunction "2_2") (pintype "passive"))
      (node (ref "R53") (pin "1") (pinfunction "1_1") (pintype "passive"))
    )
    (net (code "127") (name "Net-(IC6C-+IN)") (class "Default")
      (node (ref "C47") (pin "2") (pinfunction "2_2") (pintype "passive"))
      (node (ref "IC6") (pin "10") (pinfunction "+IN_10") (pintype "input"))
      (node (ref "R101") (pin "1") (pinfunction "1_1") (pintype "passive"))
    )
    (net (code "128") (name "Net-(IC6C--IN)") (class "Default")
      (node (ref "C46") (pin "1") (pinfunction "1_1") (pintype "passive"))
      (node (ref "IC6") (pin "9") (pinfunction "-IN_9") (pintype "input"))
      (node (ref "R99") (pin "1") (pinfunction "1_1") (pintype "passive"))
    )
    (net (code "129") (name "Net-(IC6C-OUT)") (class "Default")
      (node (ref "C46") (pin "2") (pinfunction "2_2") (pintype "passive"))
      (node (ref "IC6") (pin "8") (pinfunction "OUT_8") (pintype "output"))
      (node (ref "R70") (pin "2") (pinfunction "2_2") (pintype "passive"))
      (node (ref "R98") (pin "1") (pinfunction "1_1") (pintype "passive"))
    )
    (net (code "130") (name "Net-(IC6D-+IN)") (class "Default")
      (node (ref "C49") (pin "2") (pinfunction "2_2") (pintype "passive"))
      (node (ref "IC6") (pin "12") (pinfunction "+IN_12") (pintype "input"))
      (node (ref "R103") (pin "1") (pinfunction "1_1") (pintype "passive"))
    )
    (net (code "131") (name "Net-(IC6D--IN)") (class "Default")
      (node (ref "C50") (pin "1") (pinfunction "1_1") (pintype "passive"))
      (node (ref "IC6") (pin "13") (pinfunction "-IN_13") (pintype "input"))
      (node (ref "R71") (pin "1") (pinfunction "1_1") (pintype "passive"))
    )
    (net (code "132") (name "Net-(IC6D-OUT)") (class "Default")
      (node (ref "C50") (pin "2") (pinfunction "2_2") (pintype "passive"))
      (node (ref "IC6") (pin "14") (pinfunction "OUT_14") (pintype "output"))
      (node (ref "R106") (pin "1") (pinfunction "1_1") (pintype "passive"))
      (node (ref "R72") (pin "2") (pinfunction "2_2") (pintype "passive"))
    )
    (net (code "133") (name "Net-(Q1-B)") (class "Default")
      (node (ref "Q1") (pin "1") (pinfunction "B_1") (pintype "passive"))
      (node (ref "R62") (pin "2") (pinfunction "2_2") (pintype "passive"))
      (node (ref "R63") (pin "1") (pinfunction "1_1") (pintype "passive"))
    )
    (net (code "134") (name "Net-(Q2-B)") (class "Default")
      (node (ref "Q2") (pin "1") (pinfunction "B_1") (pintype "passive"))
      (node (ref "R68") (pin "2") (pinfunction "2_2") (pintype "passive"))
      (node (ref "R69") (pin "1") (pinfunction "1_1") (pintype "passive"))
    )
    (net (code "135") (name "Net-(Q3-B)") (class "Default")
      (node (ref "Q3") (pin "1") (pinfunction "B_1") (pintype "passive"))
      (node (ref "R73") (pin "2") (pinfunction "2_2") (pintype "passive"))
      (node (ref "R74") (pin "1") (pinfunction "1_1") (pintype "passive"))
    )
    (net (code "136") (name "Net-(U$2B-USBD_DM)") (class "Default")
      (node (ref "JP2") (pin "3") (pinfunction "3_3") (pintype "passive"))
      (node (ref "U$2") (pin "91") (pinfunction "USBD_DM_91") (pintype "bidirectional"))
    )
    (net (code "137") (name "Net-(U$2B-USBD_DP)") (class "Default")
      (node (ref "JP2") (pin "4") (pinfunction "4_4") (pintype "passive"))
      (node (ref "U$2") (pin "89") (pinfunction "USBD_DP_89") (pintype "bidirectional"))
    )
    (net (code "138") (name "Net-(U$2B-USBD_ID)") (class "Default")
      (node (ref "JP2") (pin "5") (pinfunction "5_5") (pintype "passive"))
      (node (ref "U$2") (pin "87") (pinfunction "USBD_ID_87") (pintype "bidirectional"))
    )
    (net (code "139") (name "Net-(U$2B-USBD_VBUS)") (class "Default")
      (node (ref "JP2") (pin "2") (pinfunction "2_2") (pintype "passive"))
      (node (ref "U$2") (pin "93") (pinfunction "USBD_VBUS_93") (pintype "bidirectional"))
    )
    (net (code "140") (name "Net-(U$2B-USBH_DM)") (class "Default")
      (node (ref "JP4") (pin "3") (pinfunction "3_3") (pintype "passive"))
      (node (ref "U$2") (pin "92") (pinfunction "USBH_DM_92") (pintype "bidirectional"))
    )
    (net (code "141") (name "Net-(U$2B-USBH_DP)") (class "Default")
      (node (ref "JP4") (pin "4") (pinfunction "4_4") (pintype "passive"))
      (node (ref "U$2") (pin "90") (pinfunction "USBH_DP_90") (pintype "bidirectional"))
    )
    (net (code "142") (name "Net-(U$2B-USBH_ID)") (class "Default")
      (node (ref "JP4") (pin "5") (pinfunction "5_5") (pintype "passive"))
      (node (ref "U$2") (pin "88") (pinfunction "USBH_ID_88") (pintype "bidirectional"))
    )
    (net (code "143") (name "Net-(U$2B-USBH_VBUS)") (class "Default")
      (node (ref "JP4") (pin "2") (pinfunction "2_2") (pintype "passive"))
      (node (ref "U$2") (pin "94") (pinfunction "USBH_VBUS_94") (pintype "bidirectional"))
    )
    (net (code "144") (name "OLED_BLK") (class "Default")
      (node (ref "JP5") (pin "2") (pinfunction "2_2") (pintype "passive"))
      (node (ref "U$2") (pin "77") (pinfunction "SPI4_MISO_77") (pintype "bidirectional"))
    )
    (net (code "145") (name "OLED_CS") (class "Default")
      (node (ref "JP5") (pin "3") (pinfunction "3_3") (pintype "passive"))
      (node (ref "U$2") (pin "75") (pinfunction "SPI4_MOSI_75") (pintype "bidirectional"))
    )
    (net (code "146") (name "OLED_DC") (class "Default")
      (node (ref "JP5") (pin "4") (pinfunction "4_4") (pintype "passive"))
      (node (ref "U$2") (pin "78") (pinfunction "SPI3_MISO_78") (pintype "bidirectional"))
    )
    (net (code "147") (name "OLED_MOSI") (class "Default")
      (node (ref "JP5") (pin "6") (pinfunction "6_6") (pintype "passive"))
      (node (ref "U$2") (pin "76") (pinfunction "SPI3_MOSI_76") (pintype "bidirectional"))
    )
    (net (code "148") (name "OLED_RST") (class "Default")
      (node (ref "JP5") (pin "5") (pinfunction "5_5") (pintype "passive"))
      (node (ref "U$2") (pin "69") (pinfunction "DAC1_69") (pintype "bidirectional"))
    )
    (net (code "149") (name "OLED_SCK") (class "Default")
      (node (ref "JP5") (pin "7") (pinfunction "7_7") (pintype "passive"))
      (node (ref "U$2") (pin "80") (pinfunction "SPI3_SCK_80") (pintype "bidirectional"))
    )
    (net (code "150") (name "OUT1") (class "Default")
      (node (ref "JP3") (pin "4") (pinfunction "4_4") (pintype "passive"))
      (node (ref "R23") (pin "1") (pinfunction "1_1") (pintype "passive"))
    )
    (net (code "151") (name "OUT2") (class "Default")
      (node (ref "JP3") (pin "2") (pinfunction "2_2") (pintype "passive"))
      (node (ref "R24") (pin "1") (pinfunction "1_1") (pintype "passive"))
    )
    (net (code "152") (name "OUT3") (class "Default")
      (node (ref "JP6") (pin "3") (pinfunction "3_3") (pintype "passive"))
      (node (ref "R60") (pin "1") (pinfunction "1_1") (pintype "passive"))
    )
    (net (code "153") (name "OUT4") (class "Default")
      (node (ref "JP6") (pin "2") (pinfunction "2_2") (pintype "passive"))
      (node (ref "R61") (pin "1") (pinfunction "1_1") (pintype "passive"))
    )
    (net (code "154") (name "OUT5") (class "Default")
      (node (ref "JP7") (pin "3") (pinfunction "3_3") (pintype "passive"))
      (node (ref "R64") (pin "1") (pinfunction "1_1") (pintype "passive"))
    )
    (net (code "155") (name "OUT6") (class "Default")
      (node (ref "JP7") (pin "2") (pinfunction "2_2") (pintype "passive"))
      (node (ref "R67") (pin "1") (pinfunction "1_1") (pintype "passive"))
    )
    (net (code "156") (name "OUT7") (class "Default")
      (node (ref "JP8") (pin "3") (pinfunction "3_3") (pintype "passive"))
      (node (ref "R70") (pin "1") (pinfunction "1_1") (pintype "passive"))
    )
    (net (code "157") (name "OUT8") (class "Default")
      (node (ref "JP8") (pin "2") (pinfunction "2_2") (pintype "passive"))
      (node (ref "R72") (pin "1") (pinfunction "1_1") (pintype "passive"))
    )
    (net (code "158") (name "SW1") (class "Default")
      (node (ref "JP5") (pin "11") (pinfunction "11_11") (pintype "passive"))
      (node (ref "U$2") (pin "4") (pinfunction "EXTI14_4") (pintype "bidirectional"))
    )
    (net (code "159") (name "SW2") (class "Default")
      (node (ref "JP5") (pin "10") (pinfunction "10_10") (pintype "passive"))
      (node (ref "U$2") (pin "6") (pinfunction "EXTI6_6") (pintype "bidirectional"))
    )
    (net (code "160") (name "SW3") (class "Default")
      (node (ref "JP5") (pin "9") (pinfunction "9_9") (pintype "passive"))
      (node (ref "U$2") (pin "8") (pinfunction "EXTI7_8") (pintype "bidirectional"))
    )
    (net (code "161") (name "SW4") (class "Default")
      (node (ref "JP6") (pin "7") (pinfunction "7_7") (pintype "passive"))
      (node (ref "U$2") (pin "12") (pinfunction "TIM1CH2_12") (pintype "bidirectional"))
    )
    (net (code "162") (name "SW5") (class "Default")
      (node (ref "JP7") (pin "7") (pinfunction "7_7") (pintype "passive"))
      (node (ref "U$2") (pin "11") (pinfunction "TIM1CH1_11") (pintype "bidirectional"))
    )
    (net (code "163") (name "SW6") (class "Default")
      (node (ref "JP8") (pin "7") (pinfunction "7_7") (pintype "passive"))
      (node (ref "U$2") (pin "17") (pinfunction "TIM3CH1_17") (pintype "bidirectional"))
    )
    (net (code "164") (name "TR1") (class "Default")
      (node (ref "Q1") (pin "3") (pinfunction "C_3") (pintype "passive"))
      (node (ref "U$2") (pin "26") (pinfunction "ADC5_26") (pintype "bidirectional"))
    )
    (net (code "165") (name "TR1_OUT") (class "Default")
      (node (ref "JP6") (pin "6") (pinfunction "6_6") (pintype "passive"))
      (node (ref "R62") (pin "1") (pinfunction "1_1") (pintype "passive"))
    )
    (net (code "166") (name "TR2") (class "Default")
      (node (ref "Q2") (pin "3") (pinfunction "C_3") (pintype "passive"))
      (node (ref "U$2") (pin "83") (pinfunction "USART2_TX_83") (pintype "bidirectional"))
    )
    (net (code "167") (name "TR2_OUT") (class "Default")
      (node (ref "JP7") (pin "6") (pinfunction "6_6") (pintype "passive"))
      (node (ref "R68") (pin "1") (pinfunction "1_1") (pintype "passive"))
    )
    (net (code "168") (name "TR3") (class "Default")
      (node (ref "Q3") (pin "3") (pinfunction "C_3") (pintype "passive"))
      (node (ref "U$2") (pin "81") (pinfunction "USART2_RX_81") (pintype "bidirectional"))
    )
    (net (code "169") (name "TR3_OUT") (class "Default")
      (node (ref "JP8") (pin "6") (pinfunction "6_6") (pintype "passive"))
      (node (ref "R73") (pin "1") (pinfunction "1_1") (pintype "passive"))
    )
    (net (code "170") (name "unconnected-(JP3-Pad1)") (class "Default")
      (node (ref "JP3") (pin "1") (pinfunction "1_1") (pintype "passive"))
    )
    (net (code "171") (name "unconnected-(JP3-Pad5)") (class "Default")
      (node (ref "JP3") (pin "5") (pinfunction "5_5") (pintype "passive"))
    )
    (net (code "172") (name "unconnected-(U$2A-ADC8-Pad32)") (class "Default")
      (node (ref "U$2") (pin "32") (pinfunction "ADC8_32") (pintype "bidirectional"))
    )
    (net (code "173") (name "unconnected-(U$2A-TIM3CH2-Pad18)") (class "Default")
      (node (ref "U$2") (pin "18") (pinfunction "TIM3CH2_18") (pintype "bidirectional"))
    )
    (net (code "174") (name "unconnected-(U$2B-DAC2-Pad70)") (class "Default")
      (node (ref "U$2") (pin "70") (pinfunction "DAC2_70") (pintype "bidirectional"))
    )
    (net (code "175") (name "unconnected-(U$2B-DACREF-Pad68)") (class "Default")
      (node (ref "U$2") (pin "68") (pinfunction "DACREF_68") (pintype "bidirectional"))
    )
    (net (code "176") (name "unconnected-(U$2B-SPI4_SCK-Pad79)") (class "Default")
      (node (ref "U$2") (pin "79") (pinfunction "SPI4_SCK_79") (pintype "bidirectional"))
    )
  )
)
